# module.net
KiCad netlist of a schematic drawn in EAGLE
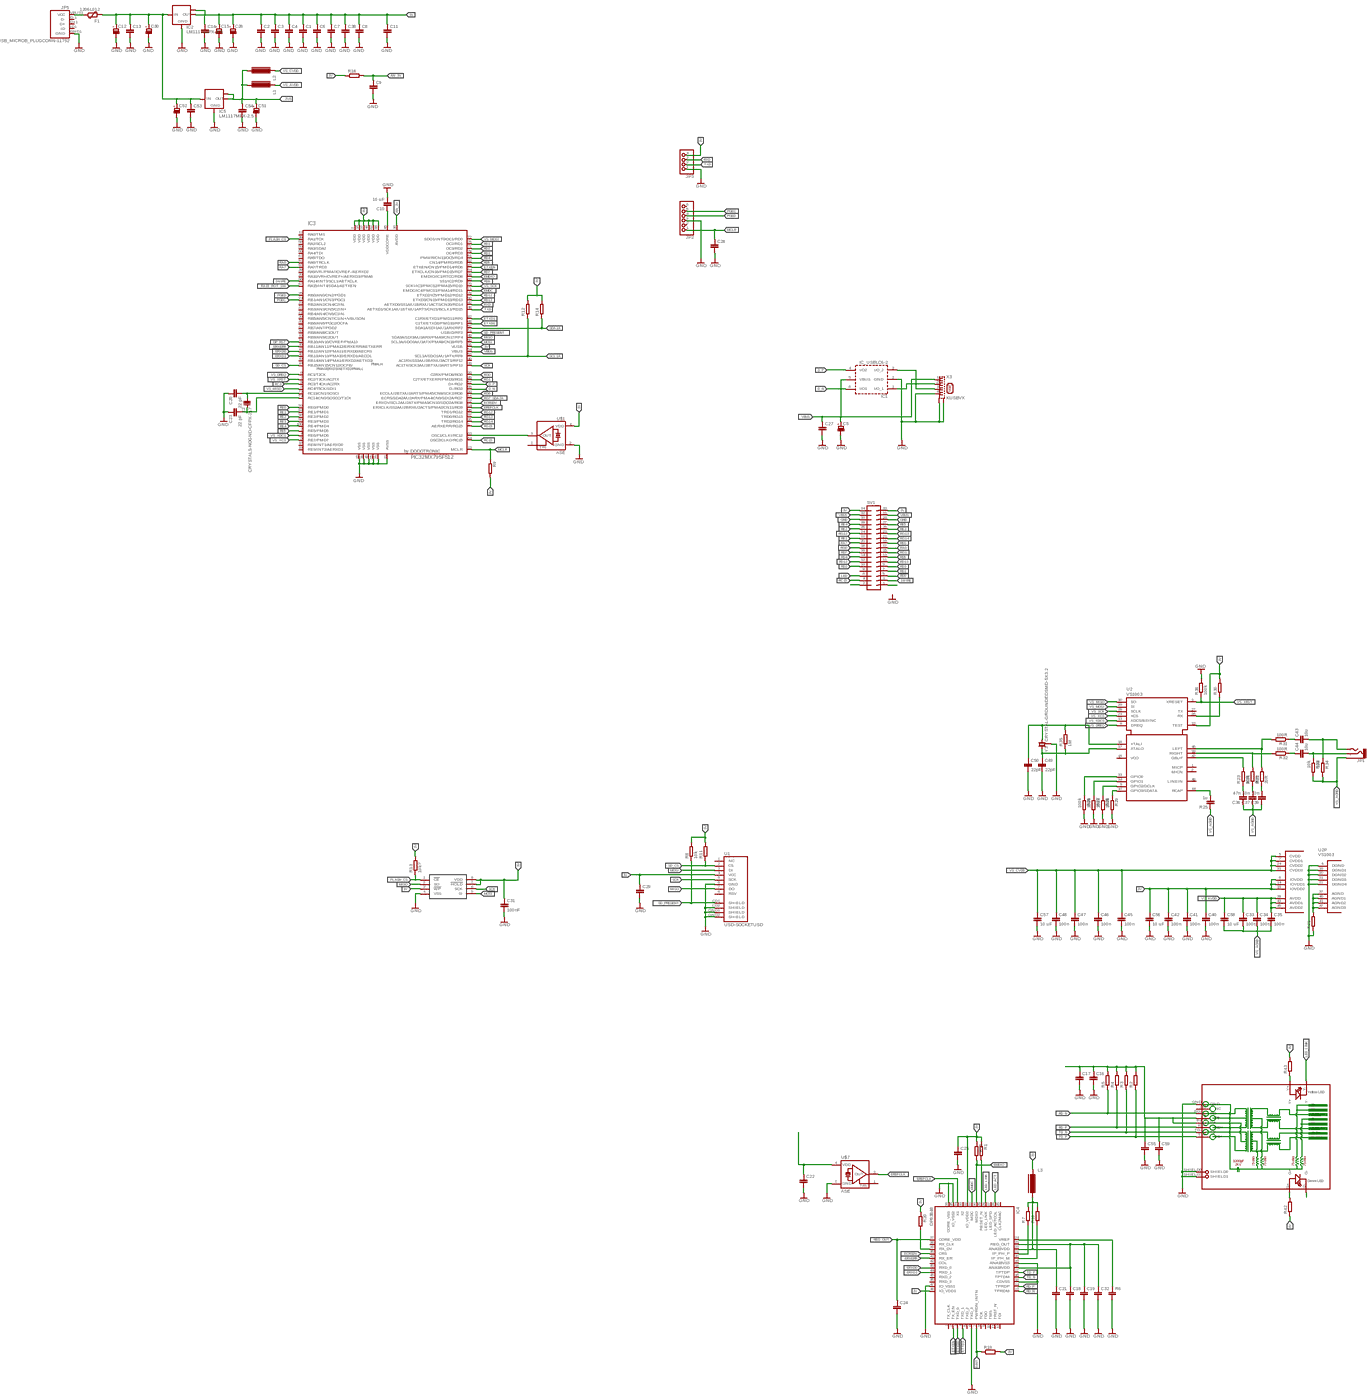
[diagram p0: schematic, sheet 1, overview]
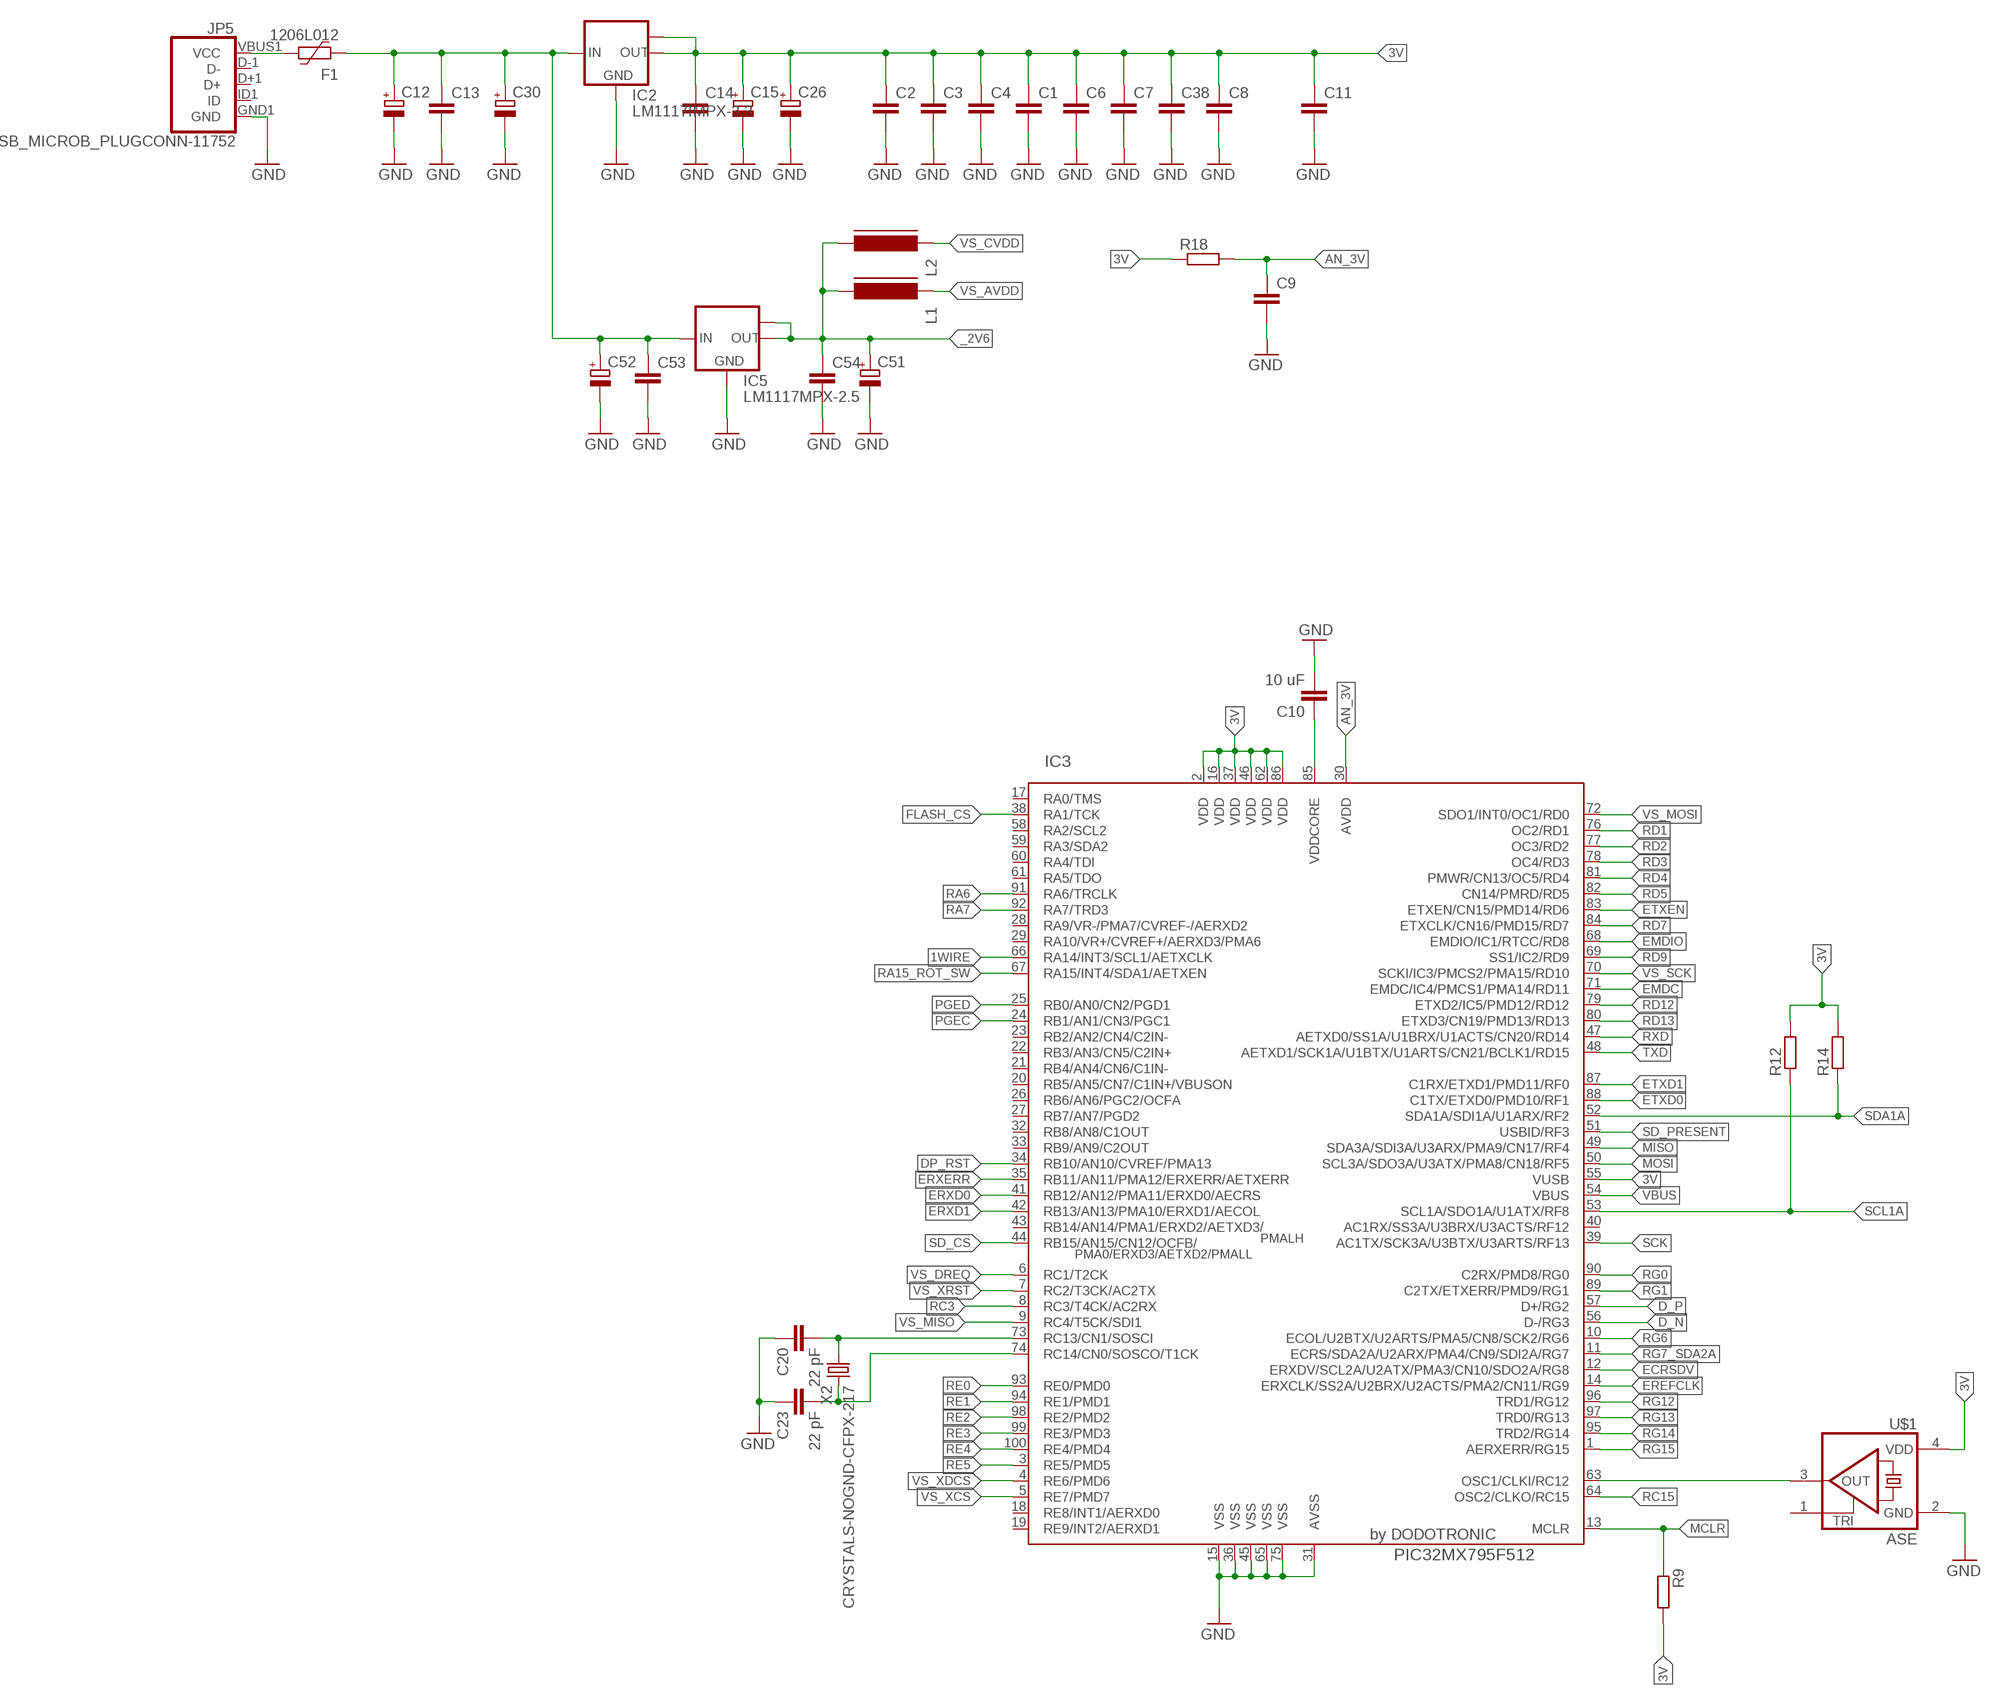
[diagram p1: schematic, sheet 1, part 1 of 4]
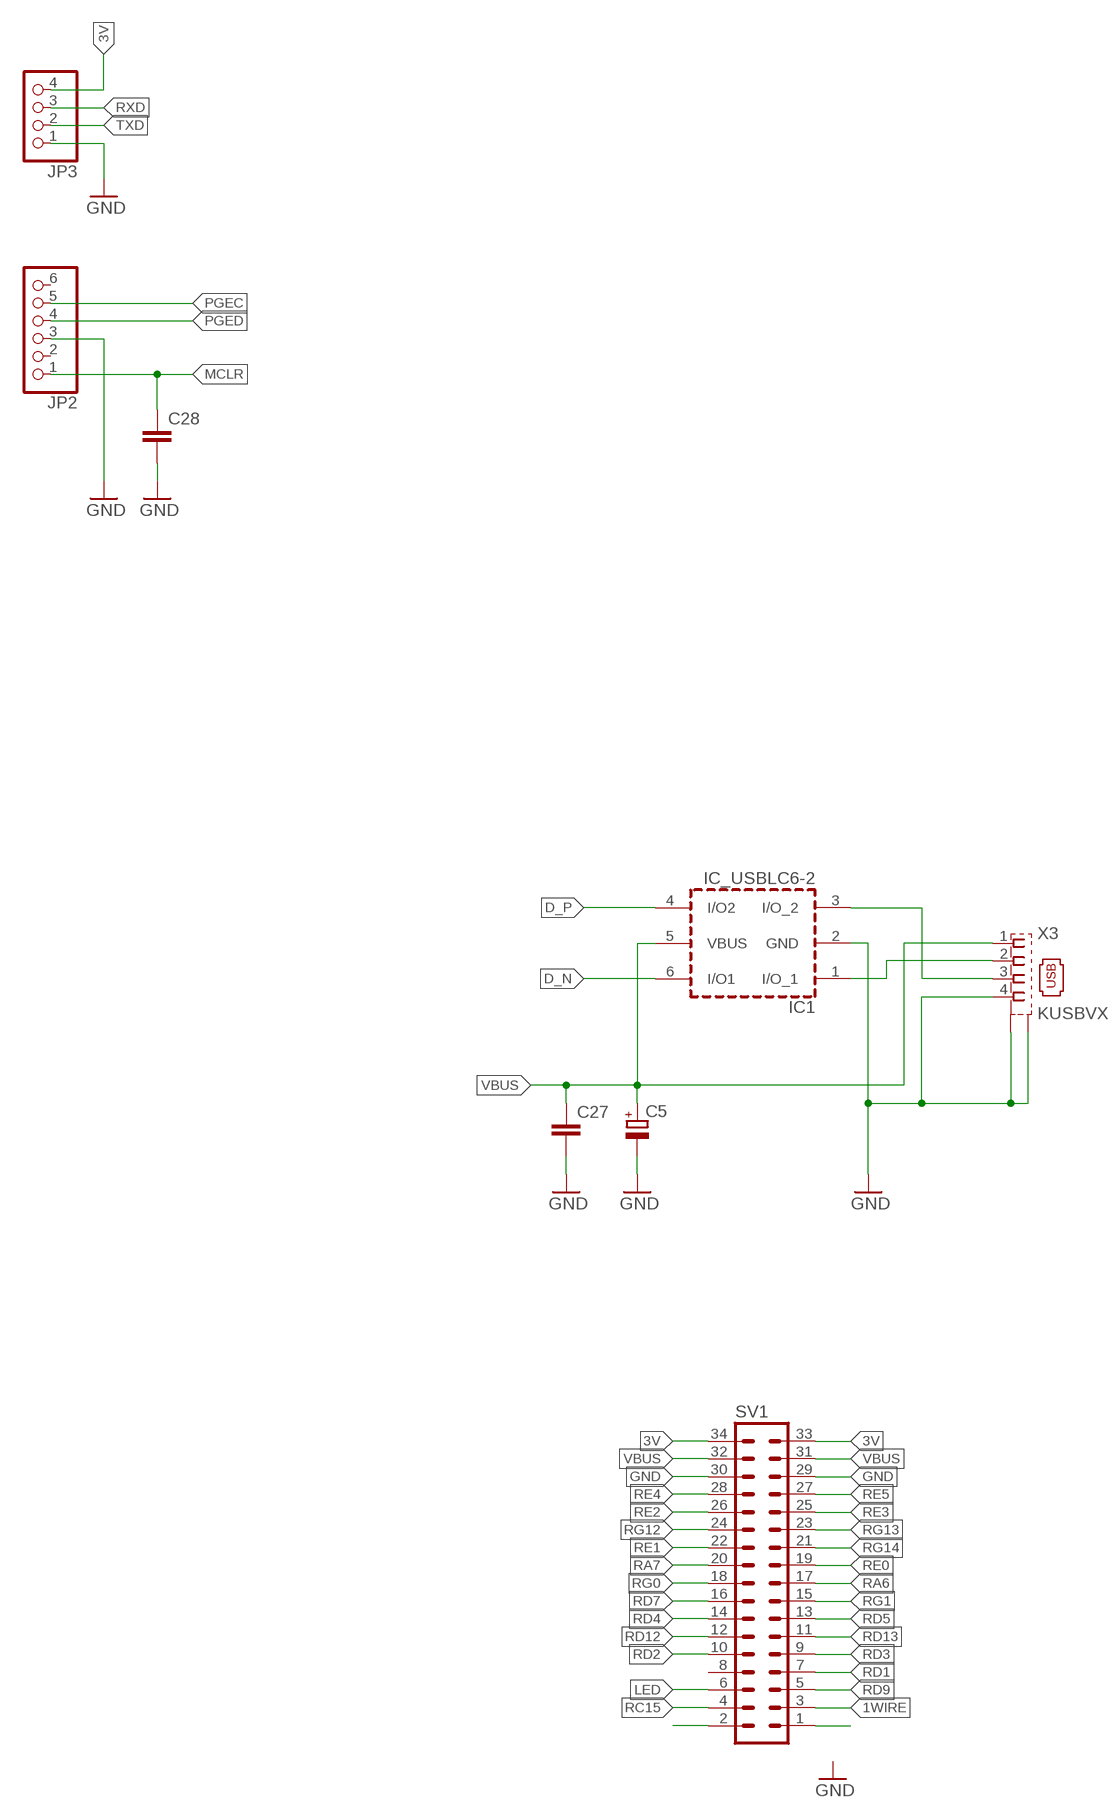
[diagram p2: schematic, sheet 1, part 2 of 4]
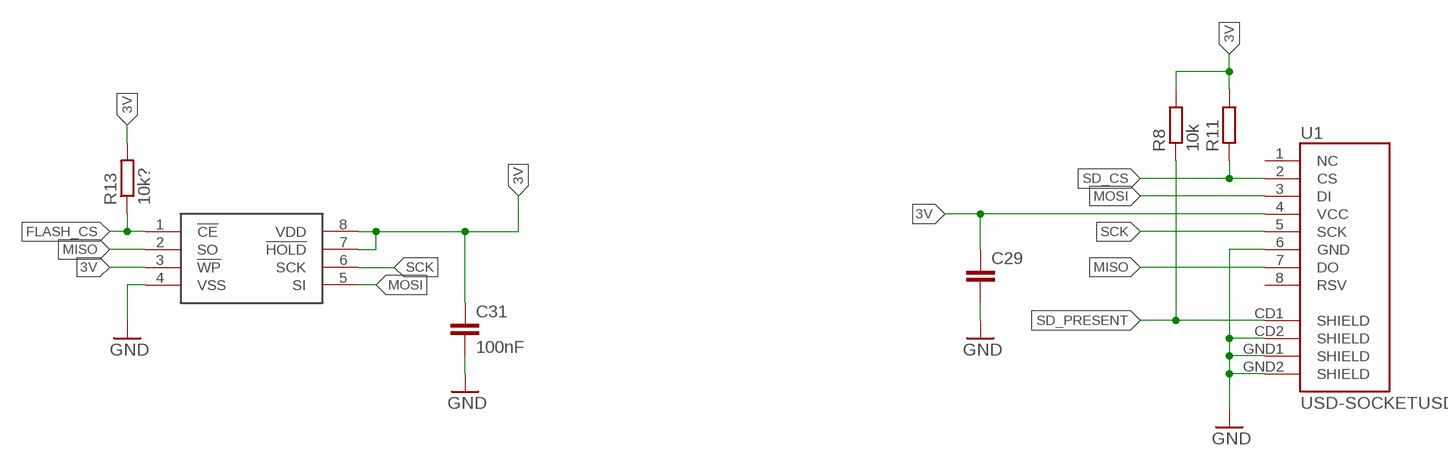
[diagram p3: schematic, sheet 1, part 3 of 4]
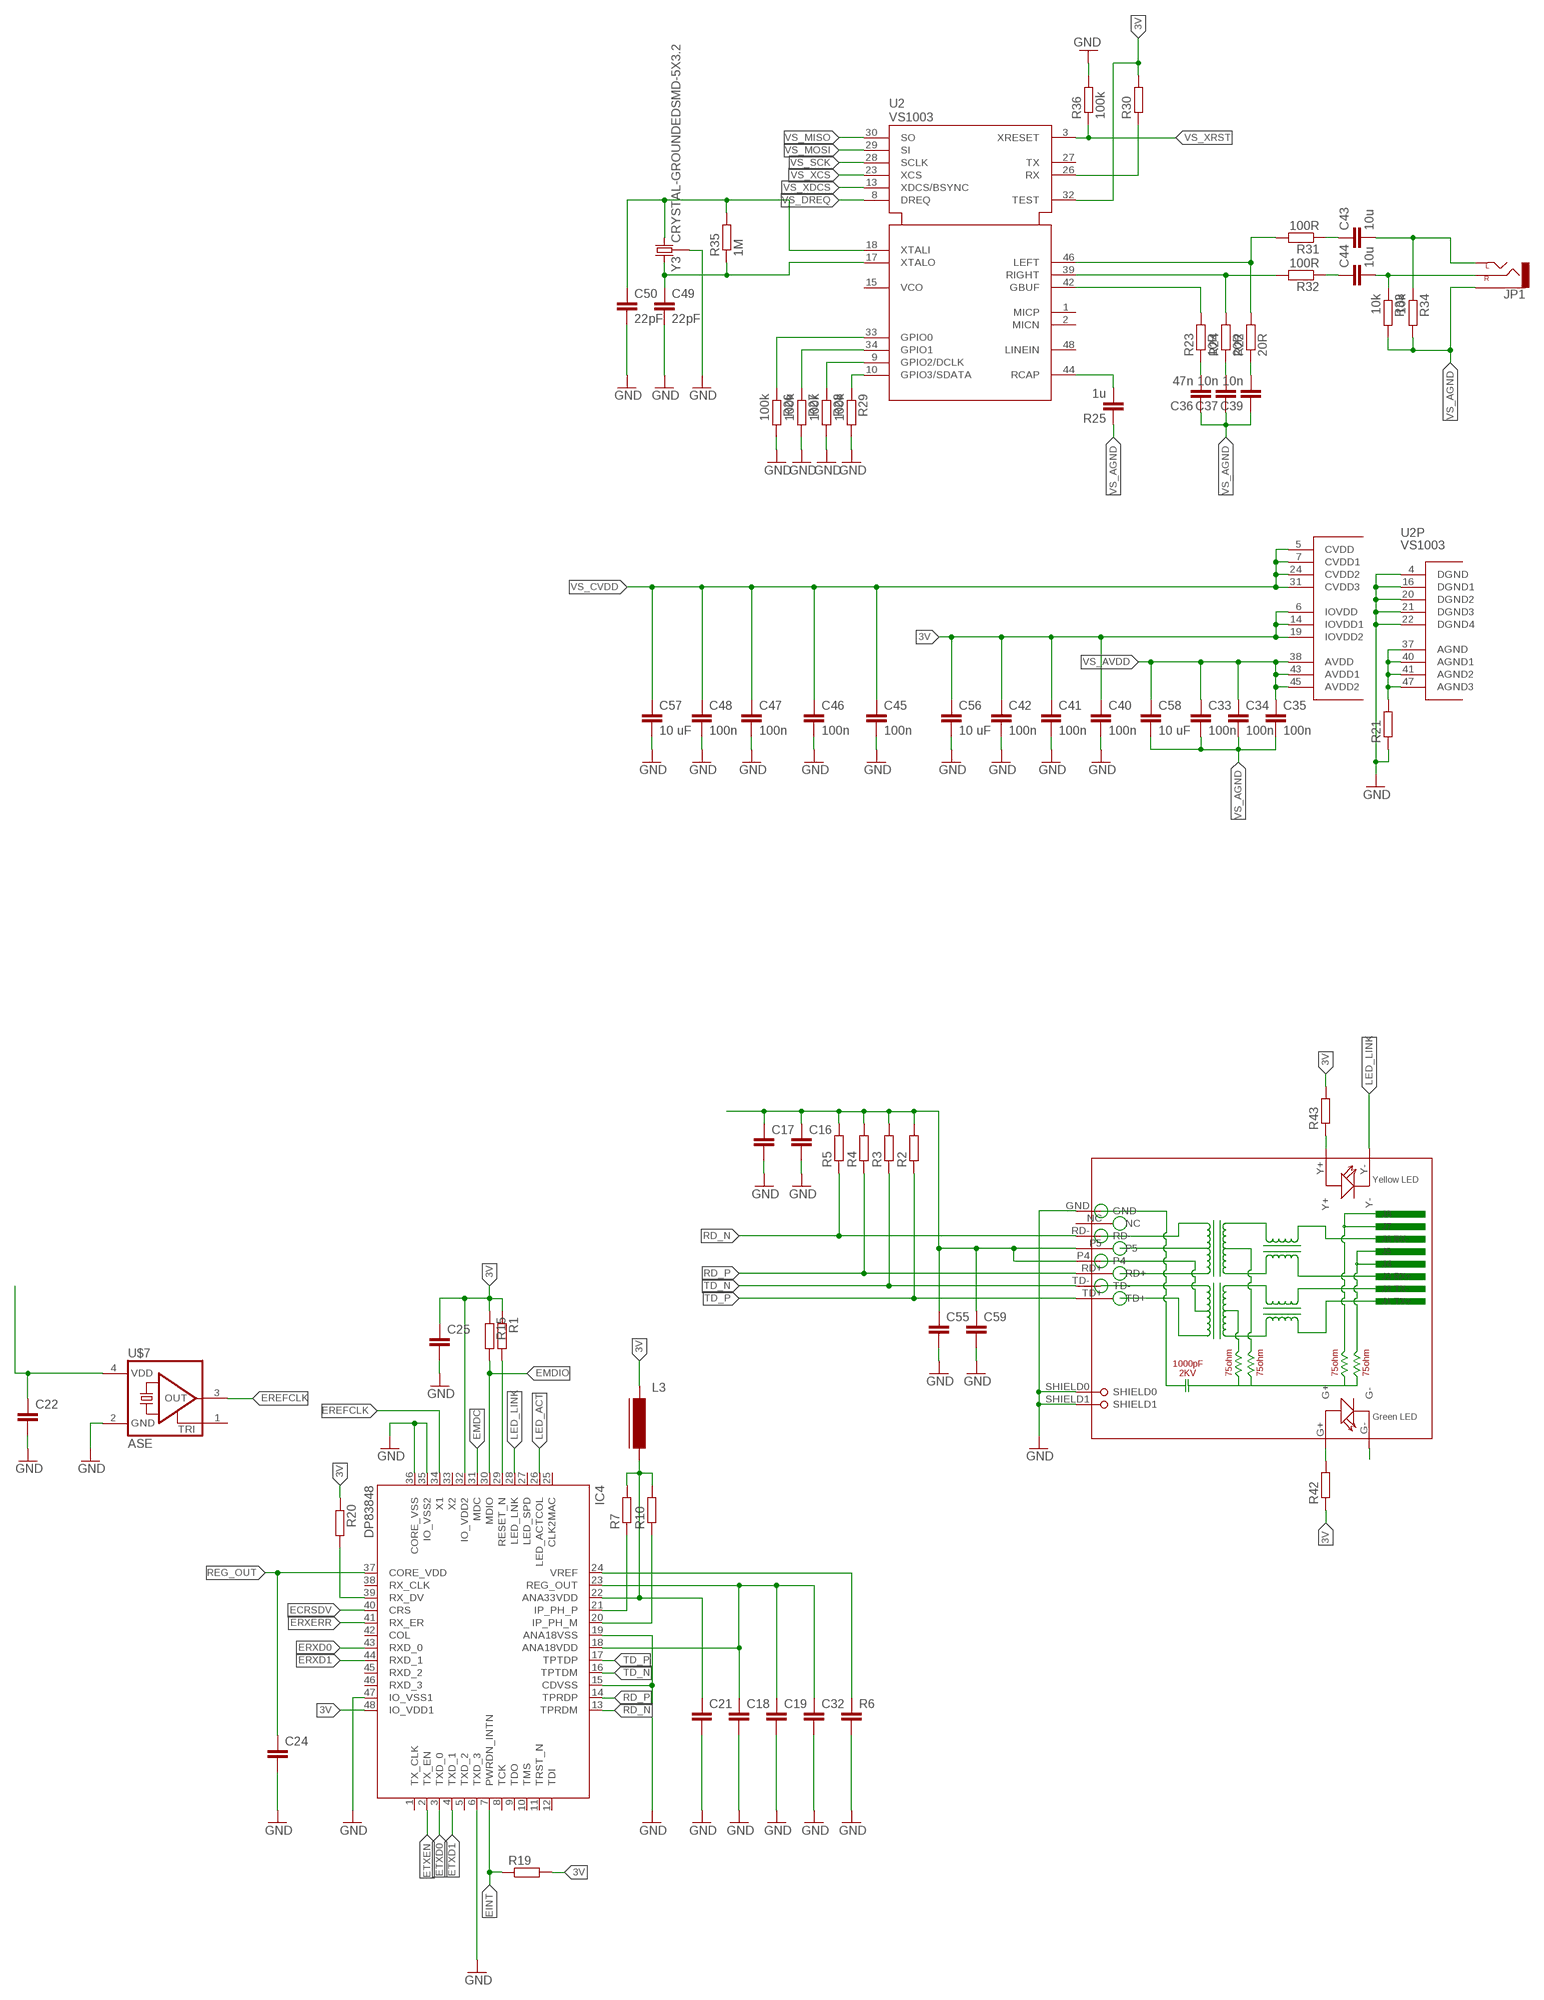
[diagram p4: schematic, sheet 1, part 4 of 4]

(export (version "E")
  (design (tool "Eeschema 10.0.6"))
  (components
    (comp (ref "C1")
      (value "C-EUC0402")
      (footprint "eagle-import:C0402")
      (libsource (lib "eagle-import") (part "C-EUC0402"))
    )
    (comp (ref "C2")
      (value "C-EUC0402")
      (footprint "eagle-import:C0402")
      (libsource (lib "eagle-import") (part "C-EUC0402"))
    )
    (comp (ref "C3")
      (value "C-EUC0402")
      (footprint "eagle-import:C0402")
      (libsource (lib "eagle-import") (part "C-EUC0402"))
    )
    (comp (ref "C4")
      (value "C-EUC0402")
      (footprint "eagle-import:C0402")
      (libsource (lib "eagle-import") (part "C-EUC0402"))
    )
    (comp (ref "C5")
      (value "CPOL-EUSMCA")
      (footprint "eagle-import:SMC_A")
      (libsource (lib "eagle-import") (part "CPOL-EUSMCA"))
    )
    (comp (ref "C6")
      (value "C-EUC0402")
      (footprint "eagle-import:C0402")
      (libsource (lib "eagle-import") (part "C-EUC0402"))
    )
    (comp (ref "C7")
      (value "C-EUC0402")
      (footprint "eagle-import:C0402")
      (libsource (lib "eagle-import") (part "C-EUC0402"))
    )
    (comp (ref "C8")
      (value "C-EUC0402")
      (footprint "eagle-import:C0402")
      (libsource (lib "eagle-import") (part "C-EUC0402"))
    )
    (comp (ref "C9")
      (value "C-EUC0402")
      (footprint "eagle-import:C0402")
      (libsource (lib "eagle-import") (part "C-EUC0402"))
    )
    (comp (ref "C10")
      (value "10 uF")
      (footprint "eagle-import:C0603")
      (libsource (lib "eagle-import") (part "C-EUC0603"))
    )
    (comp (ref "C11")
      (value "C-EUC0402")
      (footprint "eagle-import:C0402")
      (libsource (lib "eagle-import") (part "C-EUC0402"))
    )
    (comp (ref "C12")
      (value "CPOL-EUSMCB")
      (footprint "eagle-import:SMC_B")
      (libsource (lib "eagle-import") (part "CPOL-EUSMCB"))
    )
    (comp (ref "C13")
      (value "C-EUC0603")
      (footprint "eagle-import:C0603")
      (libsource (lib "eagle-import") (part "C-EUC0603"))
    )
    (comp (ref "C14")
      (value "C-EUC0603")
      (footprint "eagle-import:C0603")
      (libsource (lib "eagle-import") (part "C-EUC0603"))
    )
    (comp (ref "C15")
      (value "CPOL-EUSMCB")
      (footprint "eagle-import:SMC_B")
      (libsource (lib "eagle-import") (part "CPOL-EUSMCB"))
    )
    (comp (ref "C16")
      (value "C-EUC0603")
      (footprint "eagle-import:C0603")
      (libsource (lib "eagle-import") (part "C-EUC0603"))
    )
    (comp (ref "C17")
      (value "C-EUC0603")
      (footprint "eagle-import:C0603")
      (libsource (lib "eagle-import") (part "C-EUC0603"))
    )
    (comp (ref "C18")
      (value "C-EUC0402")
      (footprint "eagle-import:C0402")
      (libsource (lib "eagle-import") (part "C-EUC0402"))
    )
    (comp (ref "C19")
      (value "C-EUC0402")
      (footprint "eagle-import:C0402")
      (libsource (lib "eagle-import") (part "C-EUC0402"))
    )
    (comp (ref "C20")
      (value "22 pF")
      (footprint "eagle-import:C0603")
      (libsource (lib "eagle-import") (part "C-EUC0603"))
    )
    (comp (ref "C21")
      (value "C-EUC0402")
      (footprint "eagle-import:C0402")
      (libsource (lib "eagle-import") (part "C-EUC0402"))
    )
    (comp (ref "C22")
      (value "C-EUC0402")
      (footprint "eagle-import:C0402")
      (libsource (lib "eagle-import") (part "C-EUC0402"))
    )
    (comp (ref "C23")
      (value "22 pF")
      (footprint "eagle-import:C0603")
      (libsource (lib "eagle-import") (part "C-EUC0603"))
    )
    (comp (ref "C24")
      (value "C-EUC0603")
      (footprint "eagle-import:C0603")
      (libsource (lib "eagle-import") (part "C-EUC0603"))
    )
    (comp (ref "C25")
      (value "C-EUC0603")
      (footprint "eagle-import:C0603")
      (libsource (lib "eagle-import") (part "C-EUC0603"))
    )
    (comp (ref "C26")
      (value "CPOL-EUSMCA")
      (footprint "eagle-import:SMC_A")
      (libsource (lib "eagle-import") (part "CPOL-EUSMCA"))
    )
    (comp (ref "C27")
      (value "C-EUC0603")
      (footprint "eagle-import:C0603")
      (libsource (lib "eagle-import") (part "C-EUC0603"))
    )
    (comp (ref "C28")
      (value "C-EUC0603")
      (footprint "eagle-import:C0603")
      (libsource (lib "eagle-import") (part "C-EUC0603"))
    )
    (comp (ref "C29")
      (value "C-EUC0603")
      (footprint "eagle-import:C0603")
      (libsource (lib "eagle-import") (part "C-EUC0603"))
    )
    (comp (ref "C30")
      (value "CPOL-EUSMCA")
      (footprint "eagle-import:SMC_A")
      (libsource (lib "eagle-import") (part "CPOL-EUSMCA"))
    )
    (comp (ref "C31")
      (value "100nF")
      (footprint "eagle-import:C0603")
      (libsource (lib "eagle-import") (part "C-EUC0603"))
    )
    (comp (ref "C32")
      (value "C-EUC0603")
      (footprint "eagle-import:C0603")
      (libsource (lib "eagle-import") (part "C-EUC0603"))
    )
    (comp (ref "C33")
      (value "100n")
      (footprint "eagle-import:C0603")
      (libsource (lib "eagle-import") (part "C-EUC0603"))
    )
    (comp (ref "C34")
      (value "100n")
      (footprint "eagle-import:C0603")
      (libsource (lib "eagle-import") (part "C-EUC0603"))
    )
    (comp (ref "C35")
      (value "100n")
      (footprint "eagle-import:C0603")
      (libsource (lib "eagle-import") (part "C-EUC0603"))
    )
    (comp (ref "C36")
      (value "47n")
      (footprint "eagle-import:C0603")
      (libsource (lib "eagle-import") (part "C-EUC0603"))
    )
    (comp (ref "C37")
      (value "10n")
      (footprint "eagle-import:C0603")
      (libsource (lib "eagle-import") (part "C-EUC0603"))
    )
    (comp (ref "C38")
      (value "C-EUC0402")
      (footprint "eagle-import:C0402")
      (libsource (lib "eagle-import") (part "C-EUC0402"))
    )
    (comp (ref "C39")
      (value "10n")
      (footprint "eagle-import:C0603")
      (libsource (lib "eagle-import") (part "C-EUC0603"))
    )
    (comp (ref "C40")
      (value "100n")
      (footprint "eagle-import:C0402")
      (libsource (lib "eagle-import") (part "C-EUC0402"))
    )
    (comp (ref "C41")
      (value "100n")
      (footprint "eagle-import:C0402")
      (libsource (lib "eagle-import") (part "C-EUC0402"))
    )
    (comp (ref "C42")
      (value "100n")
      (footprint "eagle-import:C0402")
      (libsource (lib "eagle-import") (part "C-EUC0402"))
    )
    (comp (ref "C43")
      (value "10u")
      (footprint "eagle-import:C0603")
      (libsource (lib "eagle-import") (part "C-EUC0603"))
    )
    (comp (ref "C44")
      (value "10u")
      (footprint "eagle-import:C0603")
      (libsource (lib "eagle-import") (part "C-EUC0603"))
    )
    (comp (ref "C45")
      (value "100n")
      (footprint "eagle-import:C0402")
      (libsource (lib "eagle-import") (part "C-EUC0402"))
    )
    (comp (ref "C46")
      (value "100n")
      (footprint "eagle-import:C0603")
      (libsource (lib "eagle-import") (part "C-EUC0603"))
    )
    (comp (ref "C47")
      (value "100n")
      (footprint "eagle-import:C0603")
      (libsource (lib "eagle-import") (part "C-EUC0603"))
    )
    (comp (ref "C48")
      (value "100n")
      (footprint "eagle-import:C0603")
      (libsource (lib "eagle-import") (part "C-EUC0603"))
    )
    (comp (ref "C49")
      (value "22pF")
      (footprint "eagle-import:C0603")
      (libsource (lib "eagle-import") (part "C-EUC0603"))
    )
    (comp (ref "C50")
      (value "22pF")
      (footprint "eagle-import:C0603")
      (libsource (lib "eagle-import") (part "C-EUC0603"))
    )
    (comp (ref "C51")
      (value "CPOL-EUSMCB")
      (footprint "eagle-import:SMC_B")
      (libsource (lib "eagle-import") (part "CPOL-EUSMCB"))
    )
    (comp (ref "C52")
      (value "CPOL-EUSMCB")
      (footprint "eagle-import:SMC_B")
      (libsource (lib "eagle-import") (part "CPOL-EUSMCB"))
    )
    (comp (ref "C53")
      (value "C-EUC1206")
      (footprint "eagle-import:C1206")
      (libsource (lib "eagle-import") (part "C-EUC1206"))
    )
    (comp (ref "C54")
      (value "C-EUC1206")
      (footprint "eagle-import:C1206")
      (libsource (lib "eagle-import") (part "C-EUC1206"))
    )
    (comp (ref "C55")
      (value "C-EUC0603")
      (footprint "eagle-import:C0603")
      (libsource (lib "eagle-import") (part "C-EUC0603"))
    )
    (comp (ref "C56")
      (value "10 uF")
      (footprint "eagle-import:C0603")
      (libsource (lib "eagle-import") (part "C-EUC0603"))
    )
    (comp (ref "C57")
      (value "10 uF")
      (footprint "eagle-import:C0603")
      (libsource (lib "eagle-import") (part "C-EUC0603"))
    )
    (comp (ref "C58")
      (value "10 uF")
      (footprint "eagle-import:C0603")
      (libsource (lib "eagle-import") (part "C-EUC0603"))
    )
    (comp (ref "C59")
      (value "C-EUC0603")
      (footprint "eagle-import:C0603")
      (libsource (lib "eagle-import") (part "C-EUC0603"))
    )
    (comp (ref "F1")
      (value "1206L012")
      (footprint "eagle-import:1206L")
      (fields (field (name "MF") "Littelfuse"))
      (libsource (lib "eagle-import") (part "?1206L012"))
    )
    (comp (ref "IC1")
      (value "IC_USBLC6-2")
      (footprint "eagle-import:SOT-23-6L")
      (libsource (lib "eagle-import") (part "IC_USBLC6-2"))
    )
    (comp (ref "IC2")
      (value "LM1117IMPX-3.3")
      (footprint "eagle-import:SOT223")
      (libsource (lib "eagle-import") (part "LM1117IMPX-3.3"))
    )
    (comp (ref "IC3")
      (value "PIC32MX795F512")
      (footprint "eagle-import:TQFP100_12X12")
      (libsource (lib "eagle-import") (part "PIC32MX795F512"))
    )
    (comp (ref "IC4")
      (value "DP83848")
      (footprint "eagle-import:LQFP48")
      (fields (field (name "MPN") "DP83848VYB"))
      (libsource (lib "eagle-import") (part "DP83848"))
    )
    (comp (ref "IC5")
      (value "LM1117MPX-2.5")
      (footprint "eagle-import:SOT223")
      (libsource (lib "eagle-import") (part "LM1117MPX-2.5"))
    )
    (comp (ref "JP1")
      (value "AUDIO-JACKAUDIO_JACK2")
      (footprint "eagle-import:AUDIO-JACK2")
      (libsource (lib "eagle-import") (part "AUDIO-JACKAUDIO_JACK2"))
    )
    (comp (ref "JP2")
      (value "PINHD-1X6")
      (footprint "eagle-import:1X06")
      (libsource (lib "eagle-import") (part "PINHD-1X6"))
    )
    (comp (ref "JP3")
      (value "PINHD-1X4")
      (footprint "eagle-import:1X04")
      (libsource (lib "eagle-import") (part "PINHD-1X4"))
    )
    (comp (ref "JP5")
      (value "USB_MICROB_PLUGCONN-11752")
      (footprint "eagle-import:USB-B-MICRO-SMD_V03")
      (libsource (lib "eagle-import") (part "USB_MICROB_PLUGCONN-11752"))
    )
    (comp (ref "L1")
      (value "FERRITE-0805")
      (footprint "eagle-import:FB805")
      (libsource (lib "eagle-import") (part "FERRITE-0805"))
    )
    (comp (ref "L2")
      (value "FERRITE-0805")
      (footprint "eagle-import:FB805")
      (libsource (lib "eagle-import") (part "FERRITE-0805"))
    )
    (comp (ref "L3")
      (value "FERRITE-0805")
      (footprint "eagle-import:FB805")
      (libsource (lib "eagle-import") (part "FERRITE-0805"))
    )
    (comp (ref "R1")
      (value "R-EU_R0402")
      (footprint "eagle-import:R0402")
      (libsource (lib "eagle-import") (part "R-EU_R0402"))
    )
    (comp (ref "R2")
      (value "R-EU_R0603")
      (footprint "eagle-import:R0603")
      (libsource (lib "eagle-import") (part "R-EU_R0603"))
    )
    (comp (ref "R3")
      (value "R-EU_R0603")
      (footprint "eagle-import:R0603")
      (libsource (lib "eagle-import") (part "R-EU_R0603"))
    )
    (comp (ref "R4")
      (value "R-EU_R0603")
      (footprint "eagle-import:R0603")
      (libsource (lib "eagle-import") (part "R-EU_R0603"))
    )
    (comp (ref "R5")
      (value "R-EU_R0603")
      (footprint "eagle-import:R0603")
      (libsource (lib "eagle-import") (part "R-EU_R0603"))
    )
    (comp (ref "R6")
      (value "C-EUC0603")
      (footprint "eagle-import:C0603")
      (libsource (lib "eagle-import") (part "C-EUC0603"))
    )
    (comp (ref "R7")
      (value "R-EU_R0402")
      (footprint "eagle-import:R0402")
      (libsource (lib "eagle-import") (part "R-EU_R0402"))
    )
    (comp (ref "R8")
      (value "10k")
      (footprint "eagle-import:R0603")
      (libsource (lib "eagle-import") (part "R-EU_R0603"))
    )
    (comp (ref "R9")
      (value "R-EU_R0603")
      (footprint "eagle-import:R0603")
      (libsource (lib "eagle-import") (part "R-EU_R0603"))
    )
    (comp (ref "R10")
      (value "R-EU_R0402")
      (footprint "eagle-import:R0402")
      (libsource (lib "eagle-import") (part "R-EU_R0402"))
    )
    (comp (ref "R11")
      (value "R-EU_R0603")
      (footprint "eagle-import:R0603")
      (libsource (lib "eagle-import") (part "R-EU_R0603"))
    )
    (comp (ref "R12")
      (value "R-EU_R0603")
      (footprint "eagle-import:R0603")
      (libsource (lib "eagle-import") (part "R-EU_R0603"))
    )
    (comp (ref "R13")
      (value "10k?")
      (footprint "eagle-import:R0603")
      (libsource (lib "eagle-import") (part "R-EU_R0603"))
    )
    (comp (ref "R14")
      (value "R-EU_R0402")
      (footprint "eagle-import:R0402")
      (libsource (lib "eagle-import") (part "R-EU_R0402"))
    )
    (comp (ref "R15")
      (value "R-EU_R0603")
      (footprint "eagle-import:R0603")
      (libsource (lib "eagle-import") (part "R-EU_R0603"))
    )
    (comp (ref "R18")
      (value "R-EU_R0805")
      (footprint "eagle-import:R0805")
      (libsource (lib "eagle-import") (part "R-EU_R0805"))
    )
    (comp (ref "R19")
      (value "R-EU_R0402")
      (footprint "eagle-import:R0402")
      (libsource (lib "eagle-import") (part "R-EU_R0402"))
    )
    (comp (ref "R20")
      (value "R-EU_R0603")
      (footprint "eagle-import:R0603")
      (libsource (lib "eagle-import") (part "R-EU_R0603"))
    )
    (comp (ref "R21")
      (value "R-EU_R0603")
      (footprint "eagle-import:R0603")
      (libsource (lib "eagle-import") (part "R-EU_R0603"))
    )
    (comp (ref "R22")
      (value "20R")
      (footprint "eagle-import:R0603")
      (libsource (lib "eagle-import") (part "R-EU_R0603"))
    )
    (comp (ref "R23")
      (value "10R")
      (footprint "eagle-import:R0603")
      (libsource (lib "eagle-import") (part "R-EU_R0603"))
    )
    (comp (ref "R24")
      (value "20R")
      (footprint "eagle-import:R0603")
      (libsource (lib "eagle-import") (part "R-EU_R0603"))
    )
    (comp (ref "R25")
      (value "1u")
      (footprint "eagle-import:C0603")
      (libsource (lib "eagle-import") (part "C-EUC0603"))
    )
    (comp (ref "R26")
      (value "100k")
      (footprint "eagle-import:R0402")
      (libsource (lib "eagle-import") (part "R-EU_R0402"))
    )
    (comp (ref "R27")
      (value "100k")
      (footprint "eagle-import:R0402")
      (libsource (lib "eagle-import") (part "R-EU_R0402"))
    )
    (comp (ref "R28")
      (value "100k")
      (footprint "eagle-import:R0402")
      (libsource (lib "eagle-import") (part "R-EU_R0402"))
    )
    (comp (ref "R29")
      (value "100k")
      (footprint "eagle-import:R0402")
      (libsource (lib "eagle-import") (part "R-EU_R0402"))
    )
    (comp (ref "R30")
      (value "R-EU_0204/7")
      (footprint "eagle-import:0204_7")
      (libsource (lib "eagle-import") (part "R-EU_0204/7"))
    )
    (comp (ref "R31")
      (value "100R")
      (footprint "eagle-import:R0603")
      (libsource (lib "eagle-import") (part "R-EU_R0603"))
    )
    (comp (ref "R32")
      (value "100R")
      (footprint "eagle-import:R0603")
      (libsource (lib "eagle-import") (part "R-EU_R0603"))
    )
    (comp (ref "R33")
      (value "10k")
      (footprint "eagle-import:R0603")
      (libsource (lib "eagle-import") (part "R-EU_R0603"))
    )
    (comp (ref "R34")
      (value "10k")
      (footprint "eagle-import:R0603")
      (libsource (lib "eagle-import") (part "R-EU_R0603"))
    )
    (comp (ref "R35")
      (value "1M")
      (footprint "eagle-import:R0603")
      (libsource (lib "eagle-import") (part "R-EU_R0603"))
    )
    (comp (ref "R36")
      (value "100k")
      (footprint "eagle-import:R0603")
      (libsource (lib "eagle-import") (part "R-EU_R0603"))
    )
    (comp (ref "R42")
      (value "R-EU_R0603")
      (footprint "eagle-import:R0603")
      (libsource (lib "eagle-import") (part "R-EU_R0603"))
    )
    (comp (ref "R43")
      (value "R-EU_R0603")
      (footprint "eagle-import:R0603")
      (libsource (lib "eagle-import") (part "R-EU_R0603"))
    )
    (comp (ref "RJ1")
      (value "HR911105A")
      (footprint "eagle-import:HR911105A")
      (libsource (lib "eagle-import") (part "HR911105A"))
    )
    (comp (ref "SV1")
      (value "ML34L")
      (footprint "eagle-import:ML34L")
      (libsource (lib "eagle-import") (part "ML34L"))
    )
    (comp (ref "U$1")
      (value "ASE")
      (footprint "eagle-import:ASE")
      (libsource (lib "eagle-import") (part "ASE"))
    )
    (comp (ref "U$2")
      (value "SST25VF016BSO8M")
      (footprint "eagle-import:SO-08M")
      (libsource (lib "eagle-import") (part "SST25VF016BSO8M"))
    )
    (comp (ref "U$7")
      (value "ASE")
      (footprint "eagle-import:ASE")
      (libsource (lib "eagle-import") (part "ASE"))
    )
    (comp (ref "U1")
      (value "USD-SOCKETUSD")
      (footprint "eagle-import:USD-SOCKET-PP")
      (libsource (lib "eagle-import") (part "USD-SOCKETUSD"))
    )
    (comp (ref "U2")
      (value "VS1003")
      (footprint "eagle-import:LQFP48")
      (libsource (lib "eagle-import") (part "VS1003"))
    )
    (comp (ref "X2")
      (value "CRYSTALS-NOGND-CFPX-217")
      (footprint "eagle-import:3.2X1.5-2-PAD")
      (libsource (lib "eagle-import") (part "CRYSTALS-NOGND-CFPX-217"))
    )
    (comp (ref "X3")
      (value "KUSBVX")
      (footprint "eagle-import:KUSBVX")
      (libsource (lib "eagle-import") (part "KUSBVX"))
    )
    (comp (ref "Y3")
      (value "CRYSTAL-GROUNDEDSMD-5X3.2")
      (footprint "eagle-import:CRYSTAL-SMD-5X3.2-4PAD")
      (libsource (lib "eagle-import") (part "CRYSTAL-GROUNDEDSMD-5X3.2"))
    )
  )
  (nets
    (net (code "1") (name "/A3V") (class "Default")
      (node (ref "C16") (pin "1") (pinfunction "1_1") (pintype "passive"))
      (node (ref "C17") (pin "1") (pinfunction "1_1") (pintype "passive"))
      (node (ref "C21") (pin "1") (pinfunction "1_1") (pintype "passive"))
      (node (ref "C55") (pin "1") (pinfunction "1_1") (pintype "passive"))
      (node (ref "C59") (pin "1") (pinfunction "1_1") (pintype "passive"))
      (node (ref "IC4") (pin "22") (pinfunction "ANA33VDD_22") (pintype "power_in"))
      (node (ref "L3") (pin "2") (pinfunction "2_2") (pintype "passive"))
      (node (ref "R10") (pin "2") (pinfunction "2_2") (pintype "passive"))
      (node (ref "R2") (pin "2") (pinfunction "2_2") (pintype "passive"))
      (node (ref "R3") (pin "2") (pinfunction "2_2") (pintype "passive"))
      (node (ref "R4") (pin "2") (pinfunction "2_2") (pintype "passive"))
      (node (ref "R5") (pin "2") (pinfunction "2_2") (pintype "passive"))
      (node (ref "R7") (pin "2") (pinfunction "2_2") (pintype "passive"))
      (node (ref "RJ1") (pin "P4") (pinfunction "P4_P4") (pintype "bidirectional"))
      (node (ref "RJ1") (pin "P5") (pinfunction "P5_P5") (pintype "bidirectional"))
    )
    (net (code "2") (name "1WIRE") (class "Default")
      (node (ref "IC3") (pin "66") (pinfunction "RA14/INT3/SCL1/AETXCLK_66") (pintype "bidirectional"))
      (node (ref "SV1") (pin "3") (pinfunction "3_3") (pintype "passive"))
    )
    (net (code "3") (name "3V") (class "Default")
      (node (ref "C1") (pin "1") (pinfunction "1_1") (pintype "passive"))
      (node (ref "C11") (pin "1") (pinfunction "1_1") (pintype "passive"))
      (node (ref "C14") (pin "1") (pinfunction "1_1") (pintype "passive"))
      (node (ref "C15") (pin "+") (pinfunction "+_+") (pintype "passive"))
      (node (ref "C2") (pin "1") (pinfunction "1_1") (pintype "passive"))
      (node (ref "C22") (pin "1") (pinfunction "1_1") (pintype "passive"))
      (node (ref "C25") (pin "1") (pinfunction "1_1") (pintype "passive"))
      (node (ref "C26") (pin "+") (pinfunction "+_+") (pintype "passive"))
      (node (ref "C29") (pin "1") (pinfunction "1_1") (pintype "passive"))
      (node (ref "C3") (pin "1") (pinfunction "1_1") (pintype "passive"))
      (node (ref "C31") (pin "1") (pinfunction "1_1") (pintype "passive"))
      (node (ref "C38") (pin "1") (pinfunction "1_1") (pintype "passive"))
      (node (ref "C4") (pin "1") (pinfunction "1_1") (pintype "passive"))
      (node (ref "C40") (pin "1") (pinfunction "1_1") (pintype "passive"))
      (node (ref "C41") (pin "1") (pinfunction "1_1") (pintype "passive"))
      (node (ref "C42") (pin "1") (pinfunction "1_1") (pintype "passive"))
      (node (ref "C56") (pin "1") (pinfunction "1_1") (pintype "passive"))
      (node (ref "C6") (pin "1") (pinfunction "1_1") (pintype "passive"))
      (node (ref "C7") (pin "1") (pinfunction "1_1") (pintype "passive"))
      (node (ref "C8") (pin "1") (pinfunction "1_1") (pintype "passive"))
      (node (ref "IC2") (pin "2") (pinfunction "OUT_2") (pintype "passive"))
      (node (ref "IC2") (pin "TAB") (pinfunction "OUT1_TAB") (pintype "passive"))
      (node (ref "IC3") (pin "16") (pinfunction "VDD_16") (pintype "power_in"))
      (node (ref "IC3") (pin "2") (pinfunction "VDD_2") (pintype "power_in"))
      (node (ref "IC3") (pin "37") (pinfunction "VDD_37") (pintype "power_in"))
      (node (ref "IC3") (pin "46") (pinfunction "VDD_46") (pintype "power_in"))
      (node (ref "IC3") (pin "55") (pinfunction "VUSB_55") (pintype "bidirectional"))
      (node (ref "IC3") (pin "62") (pinfunction "VDD_62") (pintype "power_in"))
      (node (ref "IC3") (pin "86") (pinfunction "VDD_86") (pintype "power_in"))
      (node (ref "IC4") (pin "32") (pinfunction "IO_VDD2_32") (pintype "power_in"))
      (node (ref "IC4") (pin "48") (pinfunction "IO_VDD1_48") (pintype "power_in"))
      (node (ref "JP3") (pin "4") (pinfunction "4_4") (pintype "passive"))
      (node (ref "L3") (pin "1") (pinfunction "1_1") (pintype "passive"))
      (node (ref "R1") (pin "1") (pinfunction "1_1") (pintype "passive"))
      (node (ref "R11") (pin "2") (pinfunction "2_2") (pintype "passive"))
      (node (ref "R12") (pin "2") (pinfunction "2_2") (pintype "passive"))
      (node (ref "R13") (pin "2") (pinfunction "2_2") (pintype "passive"))
      (node (ref "R14") (pin "2") (pinfunction "2_2") (pintype "passive"))
      (node (ref "R15") (pin "1") (pinfunction "1_1") (pintype "passive"))
      (node (ref "R18") (pin "1") (pinfunction "1_1") (pintype "passive"))
      (node (ref "R19") (pin "2") (pinfunction "2_2") (pintype "passive"))
      (node (ref "R20") (pin "1") (pinfunction "1_1") (pintype "passive"))
      (node (ref "R30") (pin "2") (pinfunction "2_2") (pintype "passive"))
      (node (ref "R42") (pin "1") (pinfunction "1_1") (pintype "passive"))
      (node (ref "R43") (pin "2") (pinfunction "2_2") (pintype "passive"))
      (node (ref "R8") (pin "2") (pinfunction "2_2") (pintype "passive"))
      (node (ref "R9") (pin "2") (pinfunction "2_2") (pintype "passive"))
      (node (ref "SV1") (pin "33") (pinfunction "33_33") (pintype "passive"))
      (node (ref "SV1") (pin "34") (pinfunction "34_34") (pintype "passive"))
      (node (ref "U$1") (pin "4") (pinfunction "VDD_4") (pintype "power_in"))
      (node (ref "U$2") (pin "3") (pinfunction "~{WP}_3") (pintype "bidirectional"))
      (node (ref "U$2") (pin "7") (pinfunction "~{HOLD}_7") (pintype "bidirectional"))
      (node (ref "U$2") (pin "8") (pinfunction "VDD_8") (pintype "bidirectional"))
      (node (ref "U$7") (pin "4") (pinfunction "VDD_4") (pintype "power_in"))
      (node (ref "U1") (pin "4") (pinfunction "VCC_4") (pintype "bidirectional"))
      (node (ref "U2") (pin "14") (pinfunction "IOVDD1_14") (pintype "power_in"))
      (node (ref "U2") (pin "19") (pinfunction "IOVDD2_19") (pintype "power_in"))
      (node (ref "U2") (pin "32") (pinfunction "TEST_32") (pintype "bidirectional"))
      (node (ref "U2") (pin "6") (pinfunction "IOVDD_6") (pintype "power_in"))
    )
    (net (code "4") (name "AN_3V") (class "Default")
      (node (ref "C9") (pin "1") (pinfunction "1_1") (pintype "passive"))
      (node (ref "IC3") (pin "30") (pinfunction "AVDD_30") (pintype "bidirectional"))
      (node (ref "R18") (pin "2") (pinfunction "2_2") (pintype "passive"))
    )
    (net (code "5") (name "DP_RST") (class "Default")
      (node (ref "IC3") (pin "34") (pinfunction "RB10/AN10/CVREF/PMA13_34") (pintype "bidirectional"))
      (node (ref "IC4") (pin "29") (pinfunction "RESET_N_29") (pintype "input"))
      (node (ref "R1") (pin "2") (pinfunction "2_2") (pintype "passive"))
    )
    (net (code "6") (name "D_N") (class "Default")
      (node (ref "IC1") (pin "6") (pinfunction "I/O1_6") (pintype "bidirectional"))
      (node (ref "IC3") (pin "56") (pinfunction "D-/RG3_56") (pintype "bidirectional"))
    )
    (net (code "7") (name "D_P") (class "Default")
      (node (ref "IC1") (pin "4") (pinfunction "I/O2_4") (pintype "bidirectional"))
      (node (ref "IC3") (pin "57") (pinfunction "D+/RG2_57") (pintype "bidirectional"))
    )
    (net (code "8") (name "ECRSDV") (class "Default")
      (node (ref "IC3") (pin "12") (pinfunction "ERXDV/SCL2A/U2ATX/PMA3/CN10/SDO2A/RG8_12") (pintype "bidirectional"))
      (node (ref "IC4") (pin "40") (pinfunction "CRS_40") (pintype "bidirectional"))
    )
    (net (code "9") (name "EINT") (class "Default")
      (node (ref "IC4") (pin "7") (pinfunction "PWRDN_INTN_7") (pintype "bidirectional"))
      (node (ref "R19") (pin "1") (pinfunction "1_1") (pintype "passive"))
    )
    (net (code "10") (name "EMDC") (class "Default")
      (node (ref "IC3") (pin "71") (pinfunction "EMDC/IC4/PMCS1/PMA14/RD11_71") (pintype "bidirectional"))
      (node (ref "IC4") (pin "31") (pinfunction "MDC_31") (pintype "input"))
    )
    (net (code "11") (name "EMDIO") (class "Default")
      (node (ref "IC3") (pin "68") (pinfunction "EMDIO/IC1/RTCC/RD8_68") (pintype "bidirectional"))
      (node (ref "IC4") (pin "30") (pinfunction "MDIO_30") (pintype "bidirectional"))
      (node (ref "R15") (pin "2") (pinfunction "2_2") (pintype "passive"))
    )
    (net (code "12") (name "EREFCLK") (class "Default")
      (node (ref "IC3") (pin "14") (pinfunction "ERXCLK/SS2A/U2BRX/U2ACTS/PMA2/CN11/RG9_14") (pintype "bidirectional"))
      (node (ref "IC4") (pin "34") (pinfunction "X1_34") (pintype "input"))
      (node (ref "U$7") (pin "3") (pinfunction "OUT_3") (pintype "output"))
    )
    (net (code "13") (name "ERXD0") (class "Default")
      (node (ref "IC3") (pin "41") (pinfunction "RB12/AN12/PMA11/ERXD0/AECRS_41") (pintype "bidirectional"))
      (node (ref "IC4") (pin "43") (pinfunction "RXD_0_43") (pintype "bidirectional"))
    )
    (net (code "14") (name "ERXD1") (class "Default")
      (node (ref "IC3") (pin "42") (pinfunction "RB13/AN13/PMA10/ERXD1/AECOL_42") (pintype "bidirectional"))
      (node (ref "IC4") (pin "44") (pinfunction "RXD_1_44") (pintype "bidirectional"))
    )
    (net (code "15") (name "ERXERR") (class "Default")
      (node (ref "IC3") (pin "35") (pinfunction "RB11/AN11/PMA12/ERXERR/AETXERR_35") (pintype "bidirectional"))
      (node (ref "IC4") (pin "41") (pinfunction "RX_ER_41") (pintype "bidirectional"))
    )
    (net (code "16") (name "ETXD0") (class "Default")
      (node (ref "IC3") (pin "88") (pinfunction "C1TX/ETXD0/PMD10/RF1_88") (pintype "bidirectional"))
      (node (ref "IC4") (pin "3") (pinfunction "TXD_0_3") (pintype "bidirectional"))
    )
    (net (code "17") (name "ETXD1") (class "Default")
      (node (ref "IC3") (pin "87") (pinfunction "C1RX/ETXD1/PMD11/RF0_87") (pintype "bidirectional"))
      (node (ref "IC4") (pin "4") (pinfunction "TXD_1_4") (pintype "bidirectional"))
    )
    (net (code "18") (name "ETXEN") (class "Default")
      (node (ref "IC3") (pin "83") (pinfunction "ETXEN/CN15/PMD14/RD6_83") (pintype "bidirectional"))
      (node (ref "IC4") (pin "2") (pinfunction "TX_EN_2") (pintype "bidirectional"))
    )
    (net (code "19") (name "FLASH_CS") (class "Default")
      (node (ref "IC3") (pin "38") (pinfunction "RA1/TCK_38") (pintype "bidirectional"))
      (node (ref "R13") (pin "1") (pinfunction "1_1") (pintype "passive"))
      (node (ref "U$2") (pin "1") (pinfunction "~{CE}_1") (pintype "bidirectional"))
    )
    (net (code "20") (name "GND") (class "Default")
      (node (ref "C1") (pin "2") (pinfunction "2_2") (pintype "passive"))
      (node (ref "C10") (pin "2") (pinfunction "2_2") (pintype "passive"))
      (node (ref "C11") (pin "2") (pinfunction "2_2") (pintype "passive"))
      (node (ref "C12") (pin "-") (pinfunction "-_-") (pintype "passive"))
      (node (ref "C13") (pin "2") (pinfunction "2_2") (pintype "passive"))
      (node (ref "C14") (pin "2") (pinfunction "2_2") (pintype "passive"))
      (node (ref "C15") (pin "-") (pinfunction "-_-") (pintype "passive"))
      (node (ref "C16") (pin "2") (pinfunction "2_2") (pintype "passive"))
      (node (ref "C17") (pin "2") (pinfunction "2_2") (pintype "passive"))
      (node (ref "C18") (pin "2") (pinfunction "2_2") (pintype "passive"))
      (node (ref "C19") (pin "2") (pinfunction "2_2") (pintype "passive"))
      (node (ref "C2") (pin "2") (pinfunction "2_2") (pintype "passive"))
      (node (ref "C20") (pin "1") (pinfunction "1_1") (pintype "passive"))
      (node (ref "C21") (pin "2") (pinfunction "2_2") (pintype "passive"))
      (node (ref "C22") (pin "2") (pinfunction "2_2") (pintype "passive"))
      (node (ref "C23") (pin "1") (pinfunction "1_1") (pintype "passive"))
      (node (ref "C24") (pin "2") (pinfunction "2_2") (pintype "passive"))
      (node (ref "C25") (pin "2") (pinfunction "2_2") (pintype "passive"))
      (node (ref "C26") (pin "-") (pinfunction "-_-") (pintype "passive"))
      (node (ref "C27") (pin "2") (pinfunction "2_2") (pintype "passive"))
      (node (ref "C28") (pin "2") (pinfunction "2_2") (pintype "passive"))
      (node (ref "C29") (pin "2") (pinfunction "2_2") (pintype "passive"))
      (node (ref "C3") (pin "2") (pinfunction "2_2") (pintype "passive"))
      (node (ref "C30") (pin "-") (pinfunction "-_-") (pintype "passive"))
      (node (ref "C31") (pin "2") (pinfunction "2_2") (pintype "passive"))
      (node (ref "C32") (pin "2") (pinfunction "2_2") (pintype "passive"))
      (node (ref "C38") (pin "2") (pinfunction "2_2") (pintype "passive"))
      (node (ref "C4") (pin "2") (pinfunction "2_2") (pintype "passive"))
      (node (ref "C40") (pin "2") (pinfunction "2_2") (pintype "passive"))
      (node (ref "C41") (pin "2") (pinfunction "2_2") (pintype "passive"))
      (node (ref "C42") (pin "2") (pinfunction "2_2") (pintype "passive"))
      (node (ref "C45") (pin "2") (pinfunction "2_2") (pintype "passive"))
      (node (ref "C46") (pin "2") (pinfunction "2_2") (pintype "passive"))
      (node (ref "C47") (pin "2") (pinfunction "2_2") (pintype "passive"))
      (node (ref "C48") (pin "2") (pinfunction "2_2") (pintype "passive"))
      (node (ref "C49") (pin "2") (pinfunction "2_2") (pintype "passive"))
      (node (ref "C5") (pin "-") (pinfunction "-_-") (pintype "passive"))
      (node (ref "C50") (pin "2") (pinfunction "2_2") (pintype "passive"))
      (node (ref "C51") (pin "-") (pinfunction "-_-") (pintype "passive"))
      (node (ref "C52") (pin "-") (pinfunction "-_-") (pintype "passive"))
      (node (ref "C53") (pin "2") (pinfunction "2_2") (pintype "passive"))
      (node (ref "C54") (pin "2") (pinfunction "2_2") (pintype "passive"))
      (node (ref "C55") (pin "2") (pinfunction "2_2") (pintype "passive"))
      (node (ref "C56") (pin "2") (pinfunction "2_2") (pintype "passive"))
      (node (ref "C57") (pin "2") (pinfunction "2_2") (pintype "passive"))
      (node (ref "C59") (pin "2") (pinfunction "2_2") (pintype "passive"))
      (node (ref "C6") (pin "2") (pinfunction "2_2") (pintype "passive"))
      (node (ref "C7") (pin "2") (pinfunction "2_2") (pintype "passive"))
      (node (ref "C8") (pin "2") (pinfunction "2_2") (pintype "passive"))
      (node (ref "C9") (pin "2") (pinfunction "2_2") (pintype "passive"))
      (node (ref "IC1") (pin "2") (pinfunction "GND_2") (pintype "bidirectional"))
      (node (ref "IC2") (pin "1") (pinfunction "GND_1") (pintype "input"))
      (node (ref "IC3") (pin "15") (pinfunction "VSS_15") (pintype "power_in"))
      (node (ref "IC3") (pin "31") (pinfunction "AVSS_31") (pintype "bidirectional"))
      (node (ref "IC3") (pin "36") (pinfunction "VSS_36") (pintype "power_in"))
      (node (ref "IC3") (pin "45") (pinfunction "VSS_45") (pintype "power_in"))
      (node (ref "IC3") (pin "65") (pinfunction "VSS_65") (pintype "power_in"))
      (node (ref "IC3") (pin "75") (pinfunction "VSS_75") (pintype "power_in"))
      (node (ref "IC4") (pin "15") (pinfunction "CDVSS_15") (pintype "power_in"))
      (node (ref "IC4") (pin "19") (pinfunction "ANA18VSS_19") (pintype "power_in"))
      (node (ref "IC4") (pin "35") (pinfunction "IO_VSS2_35") (pintype "power_in"))
      (node (ref "IC4") (pin "36") (pinfunction "CORE_VSS_36") (pintype "power_in"))
      (node (ref "IC4") (pin "47") (pinfunction "IO_VSS1_47") (pintype "power_in"))
      (node (ref "IC4") (pin "6") (pinfunction "TXD_3_6") (pintype "bidirectional"))
      (node (ref "IC5") (pin "1") (pinfunction "GND_1") (pintype "input"))
      (node (ref "JP2") (pin "3") (pinfunction "3_3") (pintype "passive"))
      (node (ref "JP3") (pin "1") (pinfunction "1_1") (pintype "passive"))
      (node (ref "JP5") (pin "GND1") (pinfunction "GND_GND1") (pintype "bidirectional"))
      (node (ref "R21") (pin "1") (pinfunction "1_1") (pintype "passive"))
      (node (ref "R26") (pin "2") (pinfunction "2_2") (pintype "passive"))
      (node (ref "R27") (pin "2") (pinfunction "2_2") (pintype "passive"))
      (node (ref "R28") (pin "2") (pinfunction "2_2") (pintype "passive"))
      (node (ref "R29") (pin "2") (pinfunction "2_2") (pintype "passive"))
      (node (ref "R36") (pin "2") (pinfunction "2_2") (pintype "passive"))
      (node (ref "R6") (pin "2") (pinfunction "2_2") (pintype "passive"))
      (node (ref "RJ1") (pin "GND") (pinfunction "GND_GND") (pintype "bidirectional"))
      (node (ref "RJ1") (pin "SHIELD0") (pinfunction "SHIELD0_SHIELD0") (pintype "bidirectional"))
      (node (ref "RJ1") (pin "SHIELD1") (pinfunction "SHIELD1_SHIELD1") (pintype "bidirectional"))
      (node (ref "SV1") (pin "29") (pinfunction "29_29") (pintype "passive"))
      (node (ref "SV1") (pin "30") (pinfunction "30_30") (pintype "passive"))
      (node (ref "U$1") (pin "2") (pinfunction "GND_2") (pintype "power_in"))
      (node (ref "U$2") (pin "4") (pinfunction "VSS_4") (pintype "bidirectional"))
      (node (ref "U$7") (pin "2") (pinfunction "GND_2") (pintype "power_in"))
      (node (ref "U1") (pin "6") (pinfunction "GND_6") (pintype "bidirectional"))
      (node (ref "U1") (pin "CD2") (pinfunction "SHIELD_CD2") (pintype "bidirectional"))
      (node (ref "U1") (pin "GND1") (pinfunction "SHIELD_GND1") (pintype "bidirectional"))
      (node (ref "U1") (pin "GND2") (pinfunction "SHIELD_GND2") (pintype "bidirectional"))
      (node (ref "U2") (pin "16") (pinfunction "DGND1_16") (pintype "power_in"))
      (node (ref "U2") (pin "20") (pinfunction "DGND2_20") (pintype "power_in"))
      (node (ref "U2") (pin "21") (pinfunction "DGND3_21") (pintype "power_in"))
      (node (ref "U2") (pin "22") (pinfunction "DGND4_22") (pintype "power_in"))
      (node (ref "U2") (pin "4") (pinfunction "DGND_4") (pintype "power_in"))
      (node (ref "X3") (pin "4") (pinfunction "4_4") (pintype "passive"))
      (node (ref "X3") (pin "M1") (pinfunction "S1_M1") (pintype "passive"))
      (node (ref "X3") (pin "M2") (pinfunction "S2_M2") (pintype "passive"))
      (node (ref "Y3") (pin "2") (pinfunction "3_2") (pintype "passive"))
      (node (ref "Y3") (pin "4") (pinfunction "3_4") (pintype "passive"))
    )
    (net (code "21") (name "LED") (class "Default")
      (node (ref "SV1") (pin "6") (pinfunction "6_6") (pintype "passive"))
    )
    (net (code "22") (name "LED_ACT") (class "Default")
      (node (ref "IC4") (pin "26") (pinfunction "LED_ACTCOL_26") (pintype "bidirectional"))
      (node (ref "RJ1") (pin "G-") (pinfunction "G-_G-") (pintype "bidirectional"))
    )
    (net (code "23") (name "LED_LINK") (class "Default")
      (node (ref "IC4") (pin "28") (pinfunction "LED_LNK_28") (pintype "bidirectional"))
      (node (ref "RJ1") (pin "Y-") (pinfunction "Y-_Y-") (pintype "bidirectional"))
    )
    (net (code "24") (name "MCLR") (class "Default")
      (node (ref "C28") (pin "1") (pinfunction "1_1") (pintype "passive"))
      (node (ref "IC3") (pin "13") (pinfunction "MCLR_13") (pintype "bidirectional"))
      (node (ref "JP2") (pin "1") (pinfunction "1_1") (pintype "passive"))
      (node (ref "R9") (pin "1") (pinfunction "1_1") (pintype "passive"))
    )
    (net (code "25") (name "MISO") (class "Default")
      (node (ref "IC3") (pin "49") (pinfunction "SDA3A/SDI3A/U3ARX/PMA9/CN17/RF4_49") (pintype "bidirectional"))
      (node (ref "U$2") (pin "2") (pinfunction "SO_2") (pintype "bidirectional"))
      (node (ref "U1") (pin "7") (pinfunction "DO_7") (pintype "bidirectional"))
    )
    (net (code "26") (name "MOSI") (class "Default")
      (node (ref "IC3") (pin "50") (pinfunction "SCL3A/SDO3A/U3ATX/PMA8/CN18/RF5_50") (pintype "bidirectional"))
      (node (ref "U$2") (pin "5") (pinfunction "SI_5") (pintype "bidirectional"))
      (node (ref "U1") (pin "3") (pinfunction "DI_3") (pintype "bidirectional"))
    )
    (net (code "27") (name "Net-(C36-Pad2)") (class "Default")
      (node (ref "C36") (pin "2") (pinfunction "2_2") (pintype "passive"))
      (node (ref "R23") (pin "1") (pinfunction "1_1") (pintype "passive"))
    )
    (net (code "28") (name "Net-(C37-Pad2)") (class "Default")
      (node (ref "C37") (pin "2") (pinfunction "2_2") (pintype "passive"))
      (node (ref "R24") (pin "1") (pinfunction "1_1") (pintype "passive"))
    )
    (net (code "29") (name "Net-(C39-Pad2)") (class "Default")
      (node (ref "C39") (pin "2") (pinfunction "2_2") (pintype "passive"))
      (node (ref "R22") (pin "1") (pinfunction "1_1") (pintype "passive"))
    )
    (net (code "30") (name "Net-(C43-Pad1)") (class "Default")
      (node (ref "C43") (pin "1") (pinfunction "1_1") (pintype "passive"))
      (node (ref "R31") (pin "1") (pinfunction "1_1") (pintype "passive"))
    )
    (net (code "31") (name "Net-(C44-Pad1)") (class "Default")
      (node (ref "C44") (pin "1") (pinfunction "1_1") (pintype "passive"))
      (node (ref "R32") (pin "1") (pinfunction "1_1") (pintype "passive"))
    )
    (net (code "32") (name "Net-(IC1-I{slash}O_1)") (class "Default")
      (node (ref "IC1") (pin "1") (pinfunction "I/O_1_1") (pintype "bidirectional"))
      (node (ref "X3") (pin "2") (pinfunction "2_2") (pintype "passive"))
    )
    (net (code "33") (name "Net-(IC1-I{slash}O_2)") (class "Default")
      (node (ref "IC1") (pin "3") (pinfunction "I/O_2_3") (pintype "bidirectional"))
      (node (ref "X3") (pin "3") (pinfunction "3_3") (pintype "passive"))
    )
    (net (code "34") (name "Net-(IC3-OSC1{slash}CLKI{slash}RC12)") (class "Default")
      (node (ref "IC3") (pin "63") (pinfunction "OSC1/CLKI/RC12_63") (pintype "bidirectional"))
      (node (ref "U$1") (pin "3") (pinfunction "OUT_3") (pintype "output"))
    )
    (net (code "35") (name "Net-(IC3-RC13{slash}CN1{slash}SOSCI)") (class "Default")
      (node (ref "C20") (pin "2") (pinfunction "2_2") (pintype "passive"))
      (node (ref "IC3") (pin "73") (pinfunction "RC13/CN1/SOSCI_73") (pintype "bidirectional"))
      (node (ref "X2") (pin "1") (pinfunction "1_1") (pintype "passive"))
    )
    (net (code "36") (name "Net-(IC3-RC14{slash}CN0{slash}SOSCO{slash}T1CK)") (class "Default")
      (node (ref "C23") (pin "2") (pinfunction "2_2") (pintype "passive"))
      (node (ref "IC3") (pin "74") (pinfunction "RC14/CN0/SOSCO/T1CK_74") (pintype "bidirectional"))
      (node (ref "X2") (pin "2") (pinfunction "2_2") (pintype "passive"))
    )
    (net (code "37") (name "Net-(IC3-VDDCORE)") (class "Default")
      (node (ref "C10") (pin "1") (pinfunction "1_1") (pintype "passive"))
      (node (ref "IC3") (pin "85") (pinfunction "VDDCORE_85") (pintype "bidirectional"))
    )
    (net (code "38") (name "Net-(IC4-IP_PH_M)") (class "Default")
      (node (ref "IC4") (pin "20") (pinfunction "IP_PH_M_20") (pintype "input"))
      (node (ref "R10") (pin "1") (pinfunction "1_1") (pintype "passive"))
    )
    (net (code "39") (name "Net-(IC4-IP_PH_P)") (class "Default")
      (node (ref "IC4") (pin "21") (pinfunction "IP_PH_P_21") (pintype "input"))
      (node (ref "R7") (pin "1") (pinfunction "1_1") (pintype "passive"))
    )
    (net (code "40") (name "Net-(IC4-RX_DV)") (class "Default")
      (node (ref "IC4") (pin "39") (pinfunction "RX_DV_39") (pintype "bidirectional"))
      (node (ref "R20") (pin "2") (pinfunction "2_2") (pintype "passive"))
    )
    (net (code "41") (name "Net-(IC4-VREF)") (class "Default")
      (node (ref "IC4") (pin "24") (pinfunction "VREF_24") (pintype "bidirectional"))
      (node (ref "R6") (pin "1") (pinfunction "1_1") (pintype "passive"))
    )
    (net (code "42") (name "Net-(JP1-LEFT)") (class "Default")
      (node (ref "C43") (pin "2") (pinfunction "2_2") (pintype "passive"))
      (node (ref "JP1") (pin "TIP") (pinfunction "LEFT_TIP") (pintype "bidirectional"))
      (node (ref "R34") (pin "1") (pinfunction "1_1") (pintype "passive"))
    )
    (net (code "43") (name "Net-(JP1-RIGHT)") (class "Default")
      (node (ref "C44") (pin "2") (pinfunction "2_2") (pintype "passive"))
      (node (ref "JP1") (pin "RING") (pinfunction "RIGHT_RING") (pintype "bidirectional"))
      (node (ref "R33") (pin "1") (pinfunction "1_1") (pintype "passive"))
    )
    (net (code "44") (name "Net-(JP5-VCC)") (class "Default")
      (node (ref "F1") (pin "1") (pinfunction "1_1") (pintype "passive"))
      (node (ref "JP5") (pin "VBUS1") (pinfunction "VCC_VBUS1") (pintype "bidirectional"))
    )
    (net (code "45") (name "Net-(R42-Pad2)") (class "Default")
      (node (ref "R42") (pin "2") (pinfunction "2_2") (pintype "passive"))
      (node (ref "RJ1") (pin "G+") (pinfunction "G+_G+") (pintype "bidirectional"))
    )
    (net (code "46") (name "Net-(R43-Pad1)") (class "Default")
      (node (ref "R43") (pin "1") (pinfunction "1_1") (pintype "passive"))
      (node (ref "RJ1") (pin "Y+") (pinfunction "Y+_Y+") (pintype "bidirectional"))
    )
    (net (code "47") (name "Net-(U2A-GBUF)") (class "Default")
      (node (ref "R23") (pin "2") (pinfunction "2_2") (pintype "passive"))
      (node (ref "U2") (pin "42") (pinfunction "GBUF_42") (pintype "bidirectional"))
    )
    (net (code "48") (name "Net-(U2A-GPIO0)") (class "Default")
      (node (ref "R26") (pin "1") (pinfunction "1_1") (pintype "passive"))
      (node (ref "U2") (pin "33") (pinfunction "GPIO0_33") (pintype "bidirectional"))
    )
    (net (code "49") (name "Net-(U2A-GPIO1)") (class "Default")
      (node (ref "R27") (pin "1") (pinfunction "1_1") (pintype "passive"))
      (node (ref "U2") (pin "34") (pinfunction "GPIO1_34") (pintype "bidirectional"))
    )
    (net (code "50") (name "Net-(U2A-GPIO2{slash}DCLK)") (class "Default")
      (node (ref "R28") (pin "1") (pinfunction "1_1") (pintype "passive"))
      (node (ref "U2") (pin "9") (pinfunction "GPIO2/DCLK_9") (pintype "bidirectional"))
    )
    (net (code "51") (name "Net-(U2A-GPIO3{slash}SDATA)") (class "Default")
      (node (ref "R29") (pin "1") (pinfunction "1_1") (pintype "passive"))
      (node (ref "U2") (pin "10") (pinfunction "GPIO3/SDATA_10") (pintype "bidirectional"))
    )
    (net (code "52") (name "Net-(U2A-LEFT)") (class "Default")
      (node (ref "R22") (pin "2") (pinfunction "2_2") (pintype "passive"))
      (node (ref "R31") (pin "2") (pinfunction "2_2") (pintype "passive"))
      (node (ref "U2") (pin "46") (pinfunction "LEFT_46") (pintype "bidirectional"))
    )
    (net (code "53") (name "Net-(U2A-RCAP)") (class "Default")
      (node (ref "R25") (pin "2") (pinfunction "2_2") (pintype "passive"))
      (node (ref "U2") (pin "44") (pinfunction "RCAP_44") (pintype "bidirectional"))
    )
    (net (code "54") (name "Net-(U2A-RIGHT)") (class "Default")
      (node (ref "R24") (pin "2") (pinfunction "2_2") (pintype "passive"))
      (node (ref "R32") (pin "2") (pinfunction "2_2") (pintype "passive"))
      (node (ref "U2") (pin "39") (pinfunction "RIGHT_39") (pintype "bidirectional"))
    )
    (net (code "55") (name "Net-(U2A-RX)") (class "Default")
      (node (ref "R30") (pin "1") (pinfunction "1_1") (pintype "passive"))
      (node (ref "U2") (pin "26") (pinfunction "RX_26") (pintype "bidirectional"))
    )
    (net (code "56") (name "Net-(U2A-XTALI)") (class "Default")
      (node (ref "C50") (pin "1") (pinfunction "1_1") (pintype "passive"))
      (node (ref "R35") (pin "2") (pinfunction "2_2") (pintype "passive"))
      (node (ref "U2") (pin "18") (pinfunction "XTALI_18") (pintype "bidirectional"))
      (node (ref "Y3") (pin "1") (pinfunction "2_1") (pintype "passive"))
    )
    (net (code "57") (name "Net-(U2A-XTALO)") (class "Default")
      (node (ref "C49") (pin "1") (pinfunction "1_1") (pintype "passive"))
      (node (ref "R35") (pin "1") (pinfunction "1_1") (pintype "passive"))
      (node (ref "U2") (pin "17") (pinfunction "XTALO_17") (pintype "bidirectional"))
      (node (ref "Y3") (pin "3") (pinfunction "1_3") (pintype "passive"))
    )
    (net (code "58") (name "PGEC") (class "Default")
      (node (ref "IC3") (pin "24") (pinfunction "RB1/AN1/CN3/PGC1_24") (pintype "bidirectional"))
      (node (ref "JP2") (pin "5") (pinfunction "5_5") (pintype "passive"))
    )
    (net (code "59") (name "PGED") (class "Default")
      (node (ref "IC3") (pin "25") (pinfunction "RB0/AN0/CN2/PGD1_25") (pintype "bidirectional"))
      (node (ref "JP2") (pin "4") (pinfunction "4_4") (pintype "passive"))
    )
    (net (code "60") (name "RA6") (class "Default")
      (node (ref "IC3") (pin "91") (pinfunction "RA6/TRCLK_91") (pintype "bidirectional"))
      (node (ref "SV1") (pin "17") (pinfunction "17_17") (pintype "passive"))
    )
    (net (code "61") (name "RA7") (class "Default")
      (node (ref "IC3") (pin "92") (pinfunction "RA7/TRD3_92") (pintype "bidirectional"))
      (node (ref "SV1") (pin "20") (pinfunction "20_20") (pintype "passive"))
    )
    (net (code "62") (name "RA15_ROT_SW") (class "Default")
      (node (ref "IC3") (pin "67") (pinfunction "RA15/INT4/SDA1/AETXEN_67") (pintype "bidirectional"))
    )
    (net (code "63") (name "RC3") (class "Default")
      (node (ref "IC3") (pin "8") (pinfunction "RC3/T4CK/AC2RX_8") (pintype "bidirectional"))
    )
    (net (code "64") (name "RC15") (class "Default")
      (node (ref "IC3") (pin "64") (pinfunction "OSC2/CLKO/RC15_64") (pintype "bidirectional"))
      (node (ref "SV1") (pin "4") (pinfunction "4_4") (pintype "passive"))
    )
    (net (code "65") (name "RD1") (class "Default")
      (node (ref "IC3") (pin "76") (pinfunction "OC2/RD1_76") (pintype "bidirectional"))
      (node (ref "SV1") (pin "7") (pinfunction "7_7") (pintype "passive"))
    )
    (net (code "66") (name "RD2") (class "Default")
      (node (ref "IC3") (pin "77") (pinfunction "OC3/RD2_77") (pintype "bidirectional"))
      (node (ref "SV1") (pin "10") (pinfunction "10_10") (pintype "passive"))
    )
    (net (code "67") (name "RD3") (class "Default")
      (node (ref "IC3") (pin "78") (pinfunction "OC4/RD3_78") (pintype "bidirectional"))
      (node (ref "SV1") (pin "9") (pinfunction "9_9") (pintype "passive"))
    )
    (net (code "68") (name "RD4") (class "Default")
      (node (ref "IC3") (pin "81") (pinfunction "PMWR/CN13/OC5/RD4_81") (pintype "bidirectional"))
      (node (ref "SV1") (pin "14") (pinfunction "14_14") (pintype "passive"))
    )
    (net (code "69") (name "RD5") (class "Default")
      (node (ref "IC3") (pin "82") (pinfunction "CN14/PMRD/RD5_82") (pintype "bidirectional"))
      (node (ref "SV1") (pin "13") (pinfunction "13_13") (pintype "passive"))
    )
    (net (code "70") (name "RD7") (class "Default")
      (node (ref "IC3") (pin "84") (pinfunction "ETXCLK/CN16/PMD15/RD7_84") (pintype "bidirectional"))
      (node (ref "SV1") (pin "16") (pinfunction "16_16") (pintype "passive"))
    )
    (net (code "71") (name "RD9") (class "Default")
      (node (ref "IC3") (pin "69") (pinfunction "SS1/IC2/RD9_69") (pintype "bidirectional"))
      (node (ref "SV1") (pin "5") (pinfunction "5_5") (pintype "passive"))
    )
    (net (code "72") (name "RD12") (class "Default")
      (node (ref "IC3") (pin "79") (pinfunction "ETXD2/IC5/PMD12/RD12_79") (pintype "bidirectional"))
      (node (ref "SV1") (pin "12") (pinfunction "12_12") (pintype "passive"))
    )
    (net (code "73") (name "RD13") (class "Default")
      (node (ref "IC3") (pin "80") (pinfunction "ETXD3/CN19/PMD13/RD13_80") (pintype "bidirectional"))
      (node (ref "SV1") (pin "11") (pinfunction "11_11") (pintype "passive"))
    )
    (net (code "74") (name "RD_N") (class "Default")
      (node (ref "IC4") (pin "13") (pinfunction "TPRDM_13") (pintype "bidirectional"))
      (node (ref "R5") (pin "1") (pinfunction "1_1") (pintype "passive"))
      (node (ref "RJ1") (pin "RD-") (pinfunction "RD-_RD-") (pintype "bidirectional"))
    )
    (net (code "75") (name "RD_P") (class "Default")
      (node (ref "IC4") (pin "14") (pinfunction "TPRDP_14") (pintype "bidirectional"))
      (node (ref "R4") (pin "1") (pinfunction "1_1") (pintype "passive"))
      (node (ref "RJ1") (pin "RD+") (pinfunction "RD+_RD+") (pintype "bidirectional"))
    )
    (net (code "76") (name "RE0") (class "Default")
      (node (ref "IC3") (pin "93") (pinfunction "RE0/PMD0_93") (pintype "bidirectional"))
      (node (ref "SV1") (pin "19") (pinfunction "19_19") (pintype "passive"))
    )
    (net (code "77") (name "RE1") (class "Default")
      (node (ref "IC3") (pin "94") (pinfunction "RE1/PMD1_94") (pintype "bidirectional"))
      (node (ref "SV1") (pin "22") (pinfunction "22_22") (pintype "passive"))
    )
    (net (code "78") (name "RE2") (class "Default")
      (node (ref "IC3") (pin "98") (pinfunction "RE2/PMD2_98") (pintype "bidirectional"))
      (node (ref "SV1") (pin "26") (pinfunction "26_26") (pintype "passive"))
    )
    (net (code "79") (name "RE3") (class "Default")
      (node (ref "IC3") (pin "99") (pinfunction "RE3/PMD3_99") (pintype "bidirectional"))
      (node (ref "SV1") (pin "25") (pinfunction "25_25") (pintype "passive"))
    )
    (net (code "80") (name "RE4") (class "Default")
      (node (ref "IC3") (pin "100") (pinfunction "RE4/PMD4_100") (pintype "bidirectional"))
      (node (ref "SV1") (pin "28") (pinfunction "28_28") (pintype "passive"))
    )
    (net (code "81") (name "RE5") (class "Default")
      (node (ref "IC3") (pin "3") (pinfunction "RE5/PMD5_3") (pintype "bidirectional"))
      (node (ref "SV1") (pin "27") (pinfunction "27_27") (pintype "passive"))
    )
    (net (code "82") (name "REG_OUT") (class "Default")
      (node (ref "C18") (pin "1") (pinfunction "1_1") (pintype "passive"))
      (node (ref "C19") (pin "1") (pinfunction "1_1") (pintype "passive"))
      (node (ref "C24") (pin "1") (pinfunction "1_1") (pintype "passive"))
      (node (ref "C32") (pin "1") (pinfunction "1_1") (pintype "passive"))
      (node (ref "IC4") (pin "18") (pinfunction "ANA18VDD_18") (pintype "power_in"))
      (node (ref "IC4") (pin "23") (pinfunction "REG_OUT_23") (pintype "output"))
      (node (ref "IC4") (pin "37") (pinfunction "CORE_VDD_37") (pintype "power_in"))
    )
    (net (code "83") (name "RG0") (class "Default")
      (node (ref "IC3") (pin "90") (pinfunction "C2RX/PMD8/RG0_90") (pintype "bidirectional"))
      (node (ref "SV1") (pin "18") (pinfunction "18_18") (pintype "passive"))
    )
    (net (code "84") (name "RG1") (class "Default")
      (node (ref "IC3") (pin "89") (pinfunction "C2TX/ETXERR/PMD9/RG1_89") (pintype "bidirectional"))
      (node (ref "SV1") (pin "15") (pinfunction "15_15") (pintype "passive"))
    )
    (net (code "85") (name "RG6") (class "Default")
      (node (ref "IC3") (pin "10") (pinfunction "ECOL/U2BTX/U2ARTS/PMA5/CN8/SCK2/RG6_10") (pintype "bidirectional"))
    )
    (net (code "86") (name "RG7_SDA2A") (class "Default")
      (node (ref "IC3") (pin "11") (pinfunction "ECRS/SDA2A/U2ARX/PMA4/CN9/SDI2A/RG7_11") (pintype "bidirectional"))
    )
    (net (code "87") (name "RG12") (class "Default")
      (node (ref "IC3") (pin "96") (pinfunction "TRD1/RG12_96") (pintype "bidirectional"))
      (node (ref "SV1") (pin "24") (pinfunction "24_24") (pintype "passive"))
    )
    (net (code "88") (name "RG13") (class "Default")
      (node (ref "IC3") (pin "97") (pinfunction "TRD0/RG13_97") (pintype "bidirectional"))
      (node (ref "SV1") (pin "23") (pinfunction "23_23") (pintype "passive"))
    )
    (net (code "89") (name "RG14") (class "Default")
      (node (ref "IC3") (pin "95") (pinfunction "TRD2/RG14_95") (pintype "bidirectional"))
      (node (ref "SV1") (pin "21") (pinfunction "21_21") (pintype "passive"))
    )
    (net (code "90") (name "RG15") (class "Default")
      (node (ref "IC3") (pin "1") (pinfunction "AERXERR/RG15_1") (pintype "bidirectional"))
    )
    (net (code "91") (name "RXD") (class "Default")
      (node (ref "IC3") (pin "47") (pinfunction "AETXD0/SS1A/U1BRX/U1ACTS/CN20/RD14_47") (pintype "bidirectional"))
      (node (ref "JP3") (pin "3") (pinfunction "3_3") (pintype "passive"))
    )
    (net (code "92") (name "SCK") (class "Default")
      (node (ref "IC3") (pin "39") (pinfunction "AC1TX/SCK3A/U3BTX/U3ARTS/RF13_39") (pintype "bidirectional"))
      (node (ref "U$2") (pin "6") (pinfunction "SCK_6") (pintype "bidirectional"))
      (node (ref "U1") (pin "5") (pinfunction "SCK_5") (pintype "bidirectional"))
    )
    (net (code "93") (name "SCL1A") (class "Default")
      (node (ref "IC3") (pin "53") (pinfunction "SCL1A/SDO1A/U1ATX/RF8_53") (pintype "bidirectional"))
      (node (ref "R12") (pin "1") (pinfunction "1_1") (pintype "passive"))
      (node (ref "SV1") (pin "1") (pinfunction "1_1") (pintype "passive"))
    )
    (net (code "94") (name "SDA1A") (class "Default")
      (node (ref "IC3") (pin "52") (pinfunction "SDA1A/SDI1A/U1ARX/RF2_52") (pintype "bidirectional"))
      (node (ref "R14") (pin "1") (pinfunction "1_1") (pintype "passive"))
      (node (ref "SV1") (pin "2") (pinfunction "2_2") (pintype "passive"))
    )
    (net (code "95") (name "SD_CS") (class "Default")
      (node (ref "IC3") (pin "44") (pinfunction "RB15/AN15/CN12/OCFB/_44") (pintype "bidirectional"))
      (node (ref "R11") (pin "1") (pinfunction "1_1") (pintype "passive"))
      (node (ref "U1") (pin "2") (pinfunction "CS_2") (pintype "bidirectional"))
    )
    (net (code "96") (name "SD_PRESENT") (class "Default")
      (node (ref "IC3") (pin "51") (pinfunction "USBID/RF3_51") (pintype "bidirectional"))
      (node (ref "R8") (pin "1") (pinfunction "1_1") (pintype "passive"))
      (node (ref "U1") (pin "CD1") (pinfunction "SHIELD_CD1") (pintype "bidirectional"))
    )
    (net (code "97") (name "TD_N") (class "Default")
      (node (ref "IC4") (pin "16") (pinfunction "TPTDM_16") (pintype "bidirectional"))
      (node (ref "R3") (pin "1") (pinfunction "1_1") (pintype "passive"))
      (node (ref "RJ1") (pin "TD-") (pinfunction "TD-_TD-") (pintype "bidirectional"))
    )
    (net (code "98") (name "TD_P") (class "Default")
      (node (ref "IC4") (pin "17") (pinfunction "TPTDP_17") (pintype "bidirectional"))
      (node (ref "R2") (pin "1") (pinfunction "1_1") (pintype "passive"))
      (node (ref "RJ1") (pin "TD+") (pinfunction "TD+_TD+") (pintype "bidirectional"))
    )
    (net (code "99") (name "TXD") (class "Default")
      (node (ref "IC3") (pin "48") (pinfunction "AETXD1/SCK1A/U1BTX/U1ARTS/CN21/BCLK1/RD15_48") (pintype "bidirectional"))
      (node (ref "JP3") (pin "2") (pinfunction "2_2") (pintype "passive"))
    )
    (net (code "100") (name "VBUS") (class "Default")
      (node (ref "C12") (pin "+") (pinfunction "+_+") (pintype "passive"))
      (node (ref "C13") (pin "1") (pinfunction "1_1") (pintype "passive"))
      (node (ref "C27") (pin "1") (pinfunction "1_1") (pintype "passive"))
      (node (ref "C30") (pin "+") (pinfunction "+_+") (pintype "passive"))
      (node (ref "C5") (pin "+") (pinfunction "+_+") (pintype "passive"))
      (node (ref "C52") (pin "+") (pinfunction "+_+") (pintype "passive"))
      (node (ref "C53") (pin "1") (pinfunction "1_1") (pintype "passive"))
      (node (ref "F1") (pin "2") (pinfunction "2_2") (pintype "passive"))
      (node (ref "IC1") (pin "5") (pinfunction "VBUS_5") (pintype "bidirectional"))
      (node (ref "IC2") (pin "3") (pinfunction "IN_3") (pintype "input"))
      (node (ref "IC3") (pin "54") (pinfunction "VBUS_54") (pintype "bidirectional"))
      (node (ref "IC5") (pin "3") (pinfunction "IN_3") (pintype "input"))
      (node (ref "SV1") (pin "31") (pinfunction "31_31") (pintype "passive"))
      (node (ref "SV1") (pin "32") (pinfunction "32_32") (pintype "passive"))
      (node (ref "X3") (pin "1") (pinfunction "1_1") (pintype "passive"))
    )
    (net (code "101") (name "VS_AGND") (class "Default")
      (node (ref "C33") (pin "2") (pinfunction "2_2") (pintype "passive"))
      (node (ref "C34") (pin "2") (pinfunction "2_2") (pintype "passive"))
      (node (ref "C35") (pin "2") (pinfunction "2_2") (pintype "passive"))
      (node (ref "C36") (pin "1") (pinfunction "1_1") (pintype "passive"))
      (node (ref "C37") (pin "1") (pinfunction "1_1") (pintype "passive"))
      (node (ref "C39") (pin "1") (pinfunction "1_1") (pintype "passive"))
      (node (ref "C58") (pin "2") (pinfunction "2_2") (pintype "passive"))
      (node (ref "JP1") (pin "SLEEVE") (pinfunction "SLEEVE_SLEEVE") (pintype "bidirectional"))
      (node (ref "R21") (pin "2") (pinfunction "2_2") (pintype "passive"))
      (node (ref "R25") (pin "1") (pinfunction "1_1") (pintype "passive"))
      (node (ref "R33") (pin "2") (pinfunction "2_2") (pintype "passive"))
      (node (ref "R34") (pin "2") (pinfunction "2_2") (pintype "passive"))
      (node (ref "U2") (pin "37") (pinfunction "AGND_37") (pintype "power_in"))
      (node (ref "U2") (pin "40") (pinfunction "AGND1_40") (pintype "power_in"))
      (node (ref "U2") (pin "41") (pinfunction "AGND2_41") (pintype "power_in"))
      (node (ref "U2") (pin "47") (pinfunction "AGND3_47") (pintype "power_in"))
    )
    (net (code "102") (name "VS_AVDD") (class "Default")
      (node (ref "C33") (pin "1") (pinfunction "1_1") (pintype "passive"))
      (node (ref "C34") (pin "1") (pinfunction "1_1") (pintype "passive"))
      (node (ref "C35") (pin "1") (pinfunction "1_1") (pintype "passive"))
      (node (ref "C58") (pin "1") (pinfunction "1_1") (pintype "passive"))
      (node (ref "L1") (pin "1") (pinfunction "1_1") (pintype "passive"))
      (node (ref "U2") (pin "38") (pinfunction "AVDD_38") (pintype "power_in"))
      (node (ref "U2") (pin "43") (pinfunction "AVDD1_43") (pintype "power_in"))
      (node (ref "U2") (pin "45") (pinfunction "AVDD2_45") (pintype "power_in"))
    )
    (net (code "103") (name "VS_CVDD") (class "Default")
      (node (ref "C45") (pin "1") (pinfunction "1_1") (pintype "passive"))
      (node (ref "C46") (pin "1") (pinfunction "1_1") (pintype "passive"))
      (node (ref "C47") (pin "1") (pinfunction "1_1") (pintype "passive"))
      (node (ref "C48") (pin "1") (pinfunction "1_1") (pintype "passive"))
      (node (ref "C57") (pin "1") (pinfunction "1_1") (pintype "passive"))
      (node (ref "L2") (pin "1") (pinfunction "1_1") (pintype "passive"))
      (node (ref "U2") (pin "24") (pinfunction "CVDD2_24") (pintype "power_in"))
      (node (ref "U2") (pin "31") (pinfunction "CVDD3_31") (pintype "power_in"))
      (node (ref "U2") (pin "5") (pinfunction "CVDD_5") (pintype "power_in"))
      (node (ref "U2") (pin "7") (pinfunction "CVDD1_7") (pintype "power_in"))
    )
    (net (code "104") (name "VS_DREQ") (class "Default")
      (node (ref "IC3") (pin "6") (pinfunction "RC1/T2CK_6") (pintype "bidirectional"))
      (node (ref "U2") (pin "8") (pinfunction "DREQ_8") (pintype "bidirectional"))
    )
    (net (code "105") (name "VS_MISO") (class "Default")
      (node (ref "IC3") (pin "9") (pinfunction "RC4/T5CK/SDI1_9") (pintype "bidirectional"))
      (node (ref "U2") (pin "30") (pinfunction "SO_30") (pintype "bidirectional"))
    )
    (net (code "106") (name "VS_MOSI") (class "Default")
      (node (ref "IC3") (pin "72") (pinfunction "SDO1/INT0/OC1/RD0_72") (pintype "bidirectional"))
      (node (ref "U2") (pin "29") (pinfunction "SI_29") (pintype "bidirectional"))
    )
    (net (code "107") (name "VS_SCK") (class "Default")
      (node (ref "IC3") (pin "70") (pinfunction "SCKI/IC3/PMCS2/PMA15/RD10_70") (pintype "bidirectional"))
      (node (ref "U2") (pin "28") (pinfunction "SCLK_28") (pintype "bidirectional"))
    )
    (net (code "108") (name "VS_XCS") (class "Default")
      (node (ref "IC3") (pin "5") (pinfunction "RE7/PMD7_5") (pintype "bidirectional"))
      (node (ref "U2") (pin "23") (pinfunction "XCS_23") (pintype "bidirectional"))
    )
    (net (code "109") (name "VS_XDCS") (class "Default")
      (node (ref "IC3") (pin "4") (pinfunction "RE6/PMD6_4") (pintype "bidirectional"))
      (node (ref "U2") (pin "13") (pinfunction "XDCS/BSYNC_13") (pintype "bidirectional"))
    )
    (net (code "110") (name "VS_XRST") (class "Default")
      (node (ref "IC3") (pin "7") (pinfunction "RC2/T3CK/AC2TX_7") (pintype "bidirectional"))
      (node (ref "R36") (pin "1") (pinfunction "1_1") (pintype "passive"))
      (node (ref "U2") (pin "3") (pinfunction "XRESET_3") (pintype "bidirectional"))
    )
    (net (code "111") (name "_2V6") (class "Default")
      (node (ref "C51") (pin "+") (pinfunction "+_+") (pintype "passive"))
      (node (ref "C54") (pin "1") (pinfunction "1_1") (pintype "passive"))
      (node (ref "IC5") (pin "2") (pinfunction "OUT_2") (pintype "passive"))
      (node (ref "IC5") (pin "TAB") (pinfunction "OUT1_TAB") (pintype "passive"))
      (node (ref "L1") (pin "2") (pinfunction "2_2") (pintype "passive"))
      (node (ref "L2") (pin "2") (pinfunction "2_2") (pintype "passive"))
    )
    (net (code "112") (name "unconnected-(IC3-AC1RX{slash}SS3A{slash}U3BRX{slash}U3ACTS{slash}RF12-Pad40)") (class "Default")
      (node (ref "IC3") (pin "40") (pinfunction "AC1RX/SS3A/U3BRX/U3ACTS/RF12_40") (pintype "bidirectional"))
    )
    (net (code "113") (name "unconnected-(IC3-RA0{slash}TMS-Pad17)") (class "Default")
      (node (ref "IC3") (pin "17") (pinfunction "RA0/TMS_17") (pintype "bidirectional"))
    )
    (net (code "114") (name "unconnected-(IC3-RA2{slash}SCL2-Pad58)") (class "Default")
      (node (ref "IC3") (pin "58") (pinfunction "RA2/SCL2_58") (pintype "bidirectional"))
    )
    (net (code "115") (name "unconnected-(IC3-RA3{slash}SDA2-Pad59)") (class "Default")
      (node (ref "IC3") (pin "59") (pinfunction "RA3/SDA2_59") (pintype "bidirectional"))
    )
    (net (code "116") (name "unconnected-(IC3-RA4{slash}TDI-Pad60)") (class "Default")
      (node (ref "IC3") (pin "60") (pinfunction "RA4/TDI_60") (pintype "bidirectional"))
    )
    (net (code "117") (name "unconnected-(IC3-RA5{slash}TDO-Pad61)") (class "Default")
      (node (ref "IC3") (pin "61") (pinfunction "RA5/TDO_61") (pintype "bidirectional"))
    )
    (net (code "118") (name "unconnected-(IC3-RA9{slash}VR-{slash}PMA7{slash}CVREF-{slash}AERXD2-Pad28)") (class "Default")
      (node (ref "IC3") (pin "28") (pinfunction "RA9/VR-/PMA7/CVREF-/AERXD2_28") (pintype "bidirectional"))
    )
    (net (code "119") (name "unconnected-(IC3-RA10{slash}VR+{slash}CVREF+{slash}AERXD3{slash}PMA6-Pad29)") (class "Default")
      (node (ref "IC3") (pin "29") (pinfunction "RA10/VR+/CVREF+/AERXD3/PMA6_29") (pintype "bidirectional"))
    )
    (net (code "120") (name "unconnected-(IC3-RB2{slash}AN2{slash}CN4{slash}C2IN--Pad23)") (class "Default")
      (node (ref "IC3") (pin "23") (pinfunction "RB2/AN2/CN4/C2IN-_23") (pintype "bidirectional"))
    )
    (net (code "121") (name "unconnected-(IC3-RB3{slash}AN3{slash}CN5{slash}C2IN+-Pad22)") (class "Default")
      (node (ref "IC3") (pin "22") (pinfunction "RB3/AN3/CN5/C2IN+_22") (pintype "bidirectional"))
    )
    (net (code "122") (name "unconnected-(IC3-RB4{slash}AN4{slash}CN6{slash}C1IN--Pad21)") (class "Default")
      (node (ref "IC3") (pin "21") (pinfunction "RB4/AN4/CN6/C1IN-_21") (pintype "bidirectional"))
    )
    (net (code "123") (name "unconnected-(IC3-RB5{slash}AN5{slash}CN7{slash}C1IN+{slash}VBUSON-Pad20)") (class "Default")
      (node (ref "IC3") (pin "20") (pinfunction "RB5/AN5/CN7/C1IN+/VBUSON_20") (pintype "bidirectional"))
    )
    (net (code "124") (name "unconnected-(IC3-RB6{slash}AN6{slash}PGC2{slash}OCFA-Pad26)") (class "Default")
      (node (ref "IC3") (pin "26") (pinfunction "RB6/AN6/PGC2/OCFA_26") (pintype "bidirectional"))
    )
    (net (code "125") (name "unconnected-(IC3-RB7{slash}AN7{slash}PGD2-Pad27)") (class "Default")
      (node (ref "IC3") (pin "27") (pinfunction "RB7/AN7/PGD2_27") (pintype "bidirectional"))
    )
    (net (code "126") (name "unconnected-(IC3-RB8{slash}AN8{slash}C1OUT-Pad32)") (class "Default")
      (node (ref "IC3") (pin "32") (pinfunction "RB8/AN8/C1OUT_32") (pintype "bidirectional"))
    )
    (net (code "127") (name "unconnected-(IC3-RB9{slash}AN9{slash}C2OUT-Pad33)") (class "Default")
      (node (ref "IC3") (pin "33") (pinfunction "RB9/AN9/C2OUT_33") (pintype "bidirectional"))
    )
    (net (code "128") (name "unconnected-(IC3-RB14{slash}AN14{slash}PMA1{slash}ERXD2{slash}AETXD3{slash}-Pad43)") (class "Default")
      (node (ref "IC3") (pin "43") (pinfunction "RB14/AN14/PMA1/ERXD2/AETXD3/_43") (pintype "bidirectional"))
    )
    (net (code "129") (name "unconnected-(IC3-RE8{slash}INT1{slash}AERXD0-Pad18)") (class "Default")
      (node (ref "IC3") (pin "18") (pinfunction "RE8/INT1/AERXD0_18") (pintype "bidirectional"))
    )
    (net (code "130") (name "unconnected-(IC3-RE9{slash}INT2{slash}AERXD1-Pad19)") (class "Default")
      (node (ref "IC3") (pin "19") (pinfunction "RE9/INT2/AERXD1_19") (pintype "bidirectional"))
    )
    (net (code "131") (name "unconnected-(IC4-CLK2MAC-Pad25)") (class "Default")
      (node (ref "IC4") (pin "25") (pinfunction "CLK2MAC_25") (pintype "bidirectional"))
    )
    (net (code "132") (name "unconnected-(IC4-COL-Pad42)") (class "Default")
      (node (ref "IC4") (pin "42") (pinfunction "COL_42") (pintype "bidirectional"))
    )
    (net (code "133") (name "unconnected-(IC4-LED_SPD-Pad27)") (class "Default")
      (node (ref "IC4") (pin "27") (pinfunction "LED_SPD_27") (pintype "bidirectional"))
    )
    (net (code "134") (name "unconnected-(IC4-RXD_2-Pad45)") (class "Default")
      (node (ref "IC4") (pin "45") (pinfunction "RXD_2_45") (pintype "bidirectional"))
    )
    (net (code "135") (name "unconnected-(IC4-RXD_3-Pad46)") (class "Default")
      (node (ref "IC4") (pin "46") (pinfunction "RXD_3_46") (pintype "bidirectional"))
    )
    (net (code "136") (name "unconnected-(IC4-RX_CLK-Pad38)") (class "Default")
      (node (ref "IC4") (pin "38") (pinfunction "RX_CLK_38") (pintype "bidirectional"))
    )
    (net (code "137") (name "unconnected-(IC4-TCK-Pad8)") (class "Default")
      (node (ref "IC4") (pin "8") (pinfunction "TCK_8") (pintype "input"))
    )
    (net (code "138") (name "unconnected-(IC4-TDI-Pad12)") (class "Default")
      (node (ref "IC4") (pin "12") (pinfunction "TDI_12") (pintype "input"))
    )
    (net (code "139") (name "unconnected-(IC4-TDO-Pad9)") (class "Default")
      (node (ref "IC4") (pin "9") (pinfunction "TDO_9") (pintype "output"))
    )
    (net (code "140") (name "unconnected-(IC4-TMS-Pad10)") (class "Default")
      (node (ref "IC4") (pin "10") (pinfunction "TMS_10") (pintype "input"))
    )
    (net (code "141") (name "unconnected-(IC4-TRST_N-Pad11)") (class "Default")
      (node (ref "IC4") (pin "11") (pinfunction "TRST_N_11") (pintype "input"))
    )
    (net (code "142") (name "unconnected-(IC4-TXD_2-Pad5)") (class "Default")
      (node (ref "IC4") (pin "5") (pinfunction "TXD_2_5") (pintype "bidirectional"))
    )
    (net (code "143") (name "unconnected-(IC4-TX_CLK-Pad1)") (class "Default")
      (node (ref "IC4") (pin "1") (pinfunction "TX_CLK_1") (pintype "bidirectional"))
    )
    (net (code "144") (name "unconnected-(IC4-X2-Pad33)") (class "Default")
      (node (ref "IC4") (pin "33") (pinfunction "X2_33") (pintype "output"))
    )
    (net (code "145") (name "unconnected-(JP2-Pad2)") (class "Default")
      (node (ref "JP2") (pin "2") (pinfunction "2_2") (pintype "passive"))
    )
    (net (code "146") (name "unconnected-(JP2-Pad6)") (class "Default")
      (node (ref "JP2") (pin "6") (pinfunction "6_6") (pintype "passive"))
    )
    (net (code "147") (name "unconnected-(JP5-D+-PadD+1)") (class "Default")
      (node (ref "JP5") (pin "D+1") (pinfunction "D+_D+1") (pintype "bidirectional"))
    )
    (net (code "148") (name "unconnected-(JP5-D--PadD-1)") (class "Default")
      (node (ref "JP5") (pin "D-1") (pinfunction "D-_D-1") (pintype "bidirectional"))
    )
    (net (code "149") (name "unconnected-(JP5-ID-PadID1)") (class "Default")
      (node (ref "JP5") (pin "ID1") (pinfunction "ID_ID1") (pintype "bidirectional"))
    )
    (net (code "150") (name "unconnected-(RJ1-PadNC)") (class "Default")
      (node (ref "RJ1") (pin "NC") (pinfunction "NC_NC") (pintype "bidirectional"))
    )
    (net (code "151") (name "unconnected-(SV1-Pad8)") (class "Default")
      (node (ref "SV1") (pin "8") (pinfunction "8_8") (pintype "passive"))
    )
    (net (code "152") (name "unconnected-(U$1-TRI-Pad1)") (class "Default")
      (node (ref "U$1") (pin "1") (pinfunction "TRI_1") (pintype "input"))
    )
    (net (code "153") (name "unconnected-(U$7-TRI-Pad1)") (class "Default")
      (node (ref "U$7") (pin "1") (pinfunction "TRI_1") (pintype "input"))
    )
    (net (code "154") (name "unconnected-(U1-NC-Pad1)") (class "Default")
      (node (ref "U1") (pin "1") (pinfunction "NC_1") (pintype "bidirectional"))
    )
    (net (code "155") (name "unconnected-(U1-RSV-Pad8)") (class "Default")
      (node (ref "U1") (pin "8") (pinfunction "RSV_8") (pintype "bidirectional"))
    )
    (net (code "156") (name "unconnected-(U2A-LINEIN-Pad48)") (class "Default")
      (node (ref "U2") (pin "48") (pinfunction "LINEIN_48") (pintype "bidirectional"))
    )
    (net (code "157") (name "unconnected-(U2A-MICN-Pad2)") (class "Default")
      (node (ref "U2") (pin "2") (pinfunction "MICN_2") (pintype "bidirectional"))
    )
    (net (code "158") (name "unconnected-(U2A-MICP-Pad1)") (class "Default")
      (node (ref "U2") (pin "1") (pinfunction "MICP_1") (pintype "bidirectional"))
    )
    (net (code "159") (name "unconnected-(U2A-TX-Pad27)") (class "Default")
      (node (ref "U2") (pin "27") (pinfunction "TX_27") (pintype "bidirectional"))
    )
    (net (code "160") (name "unconnected-(U2A-VCO-Pad15)") (class "Default")
      (node (ref "U2") (pin "15") (pinfunction "VCO_15") (pintype "bidirectional"))
    )
  )
)
